# 30_PSFB_Converter.net
KiCad netlist of a schematic drawn in Altium Designer
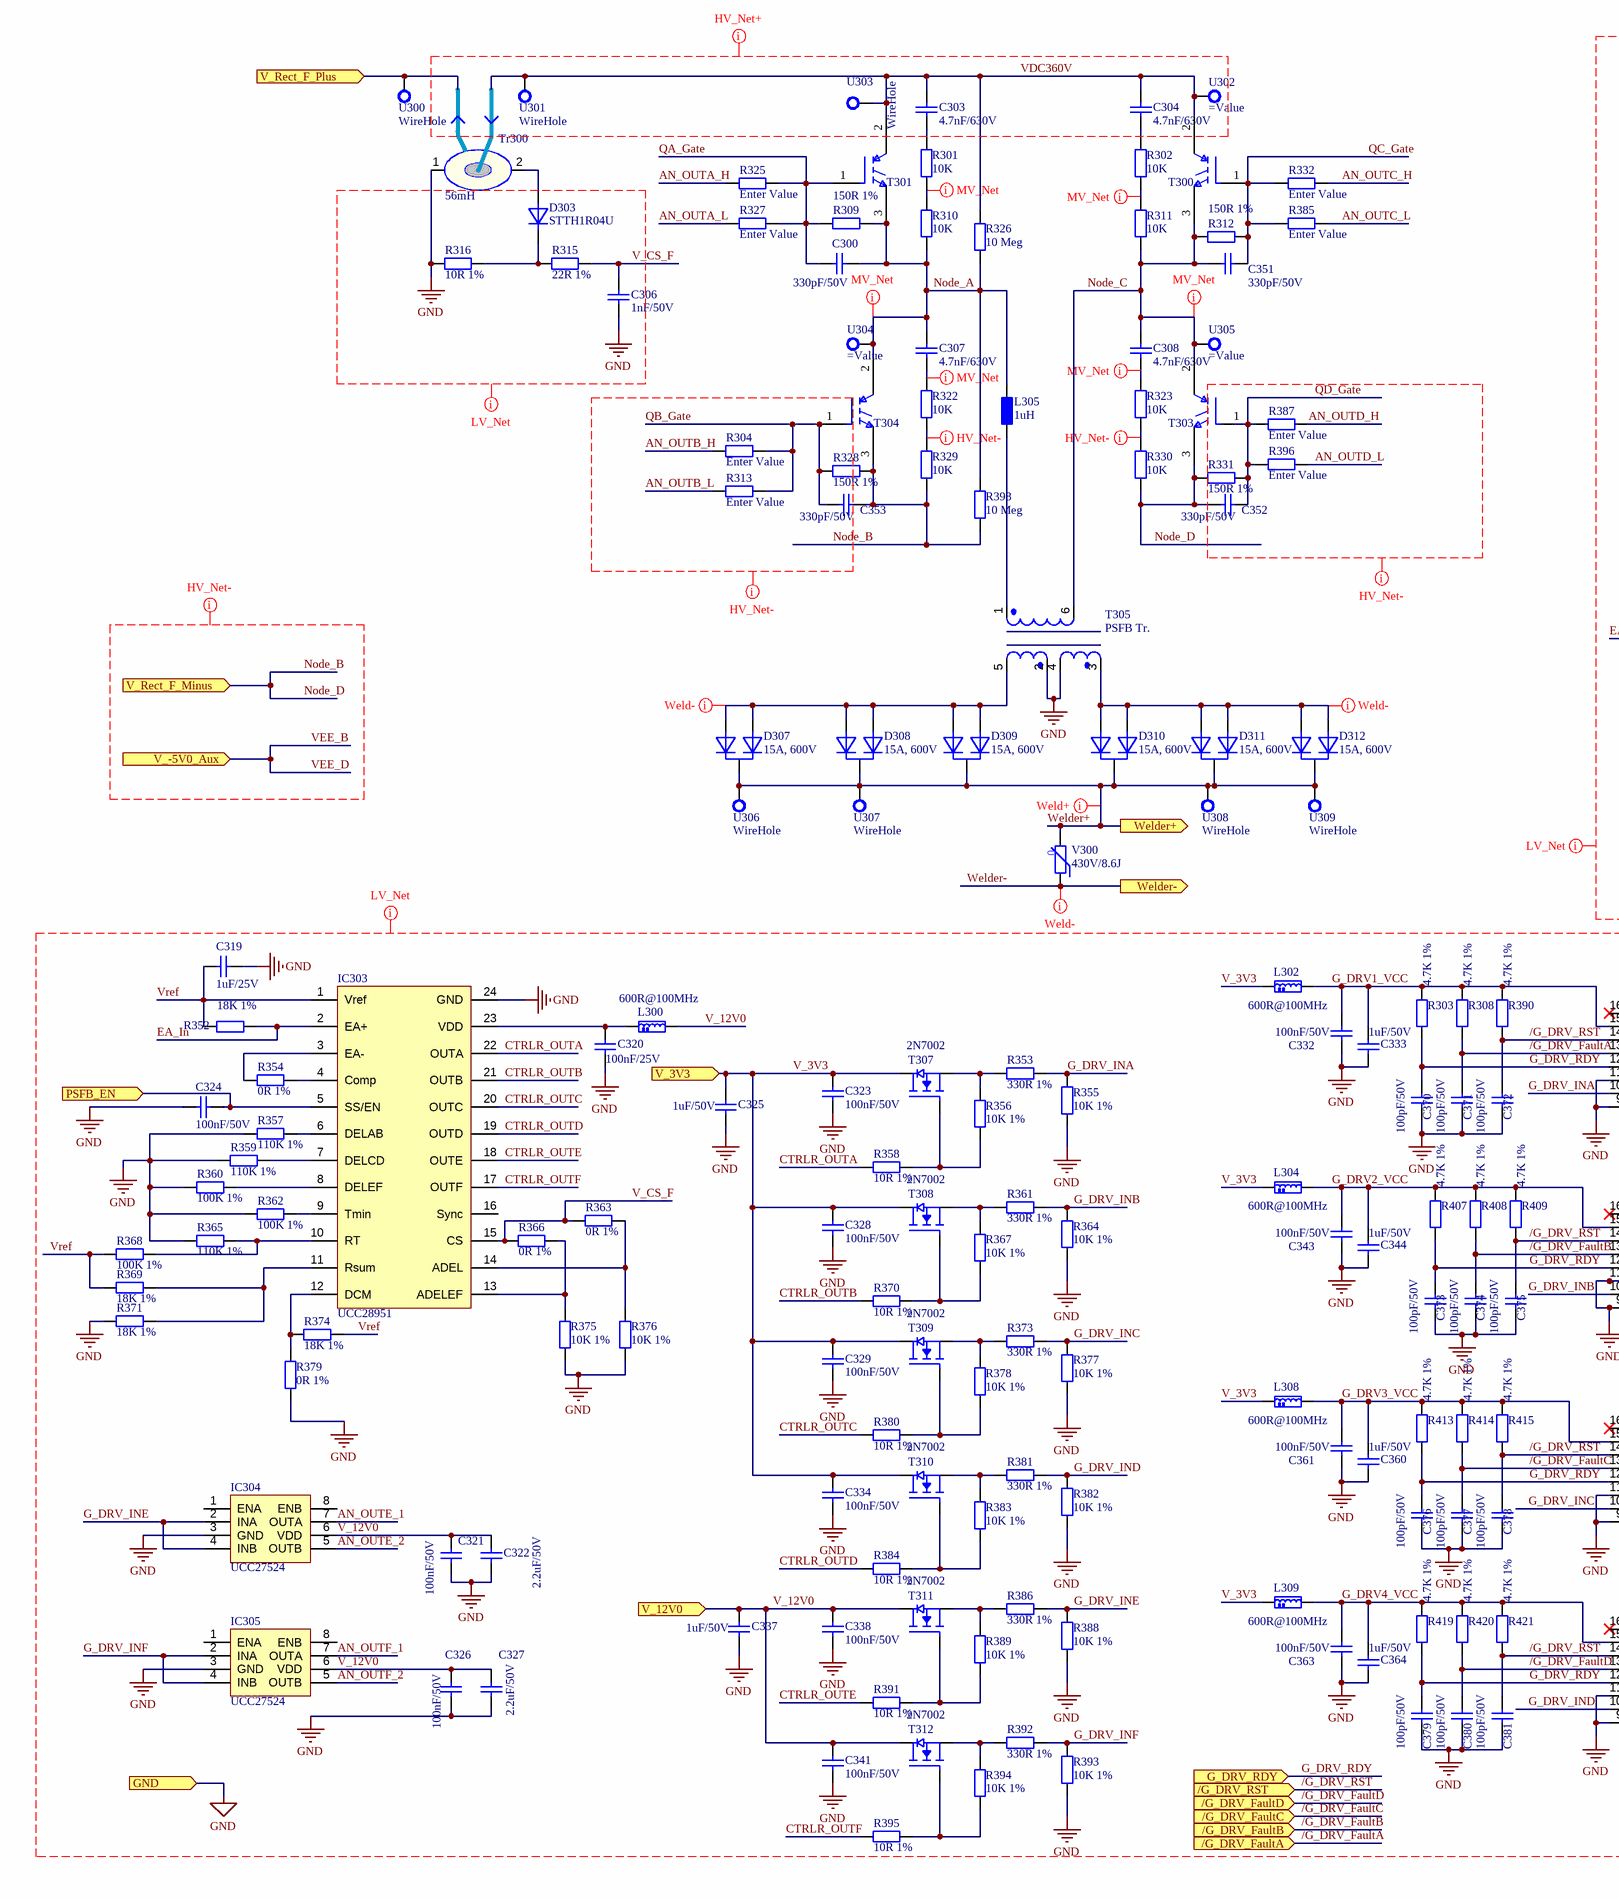
[diagram p0: 30_PSFB_Converter.SchDoc, left]
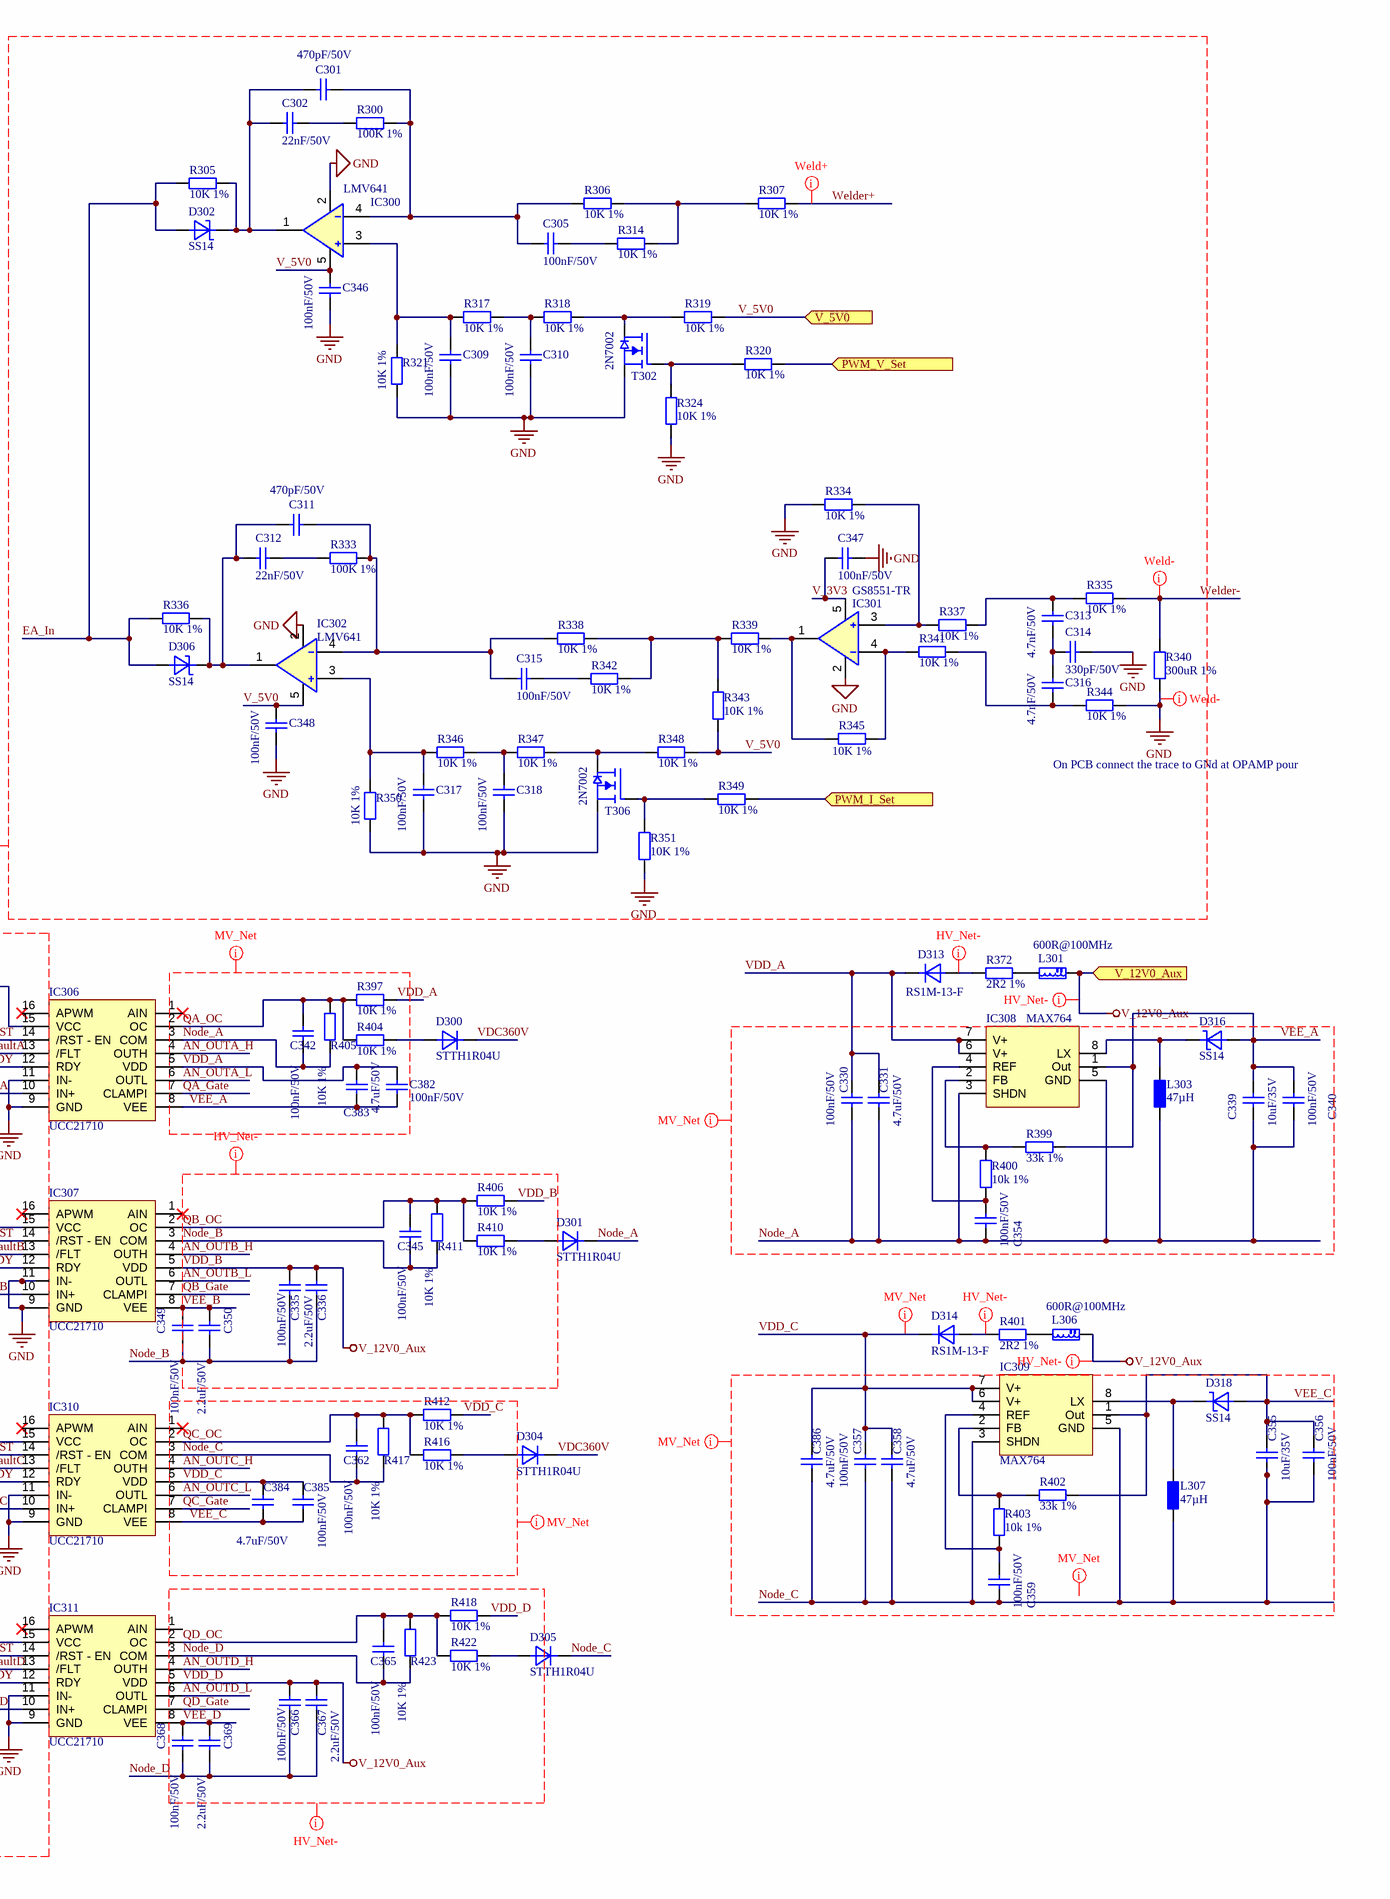
[diagram p1: 30_PSFB_Converter.SchDoc, right]

(export (version "E")
  (design (tool "Eeschema 10.0.6"))
  (components
    (comp (ref "C300")
      (value "330pF/50V")
      (footprint "EIA0603")
      (description "Generic 0603 ceramic capacitor")
      (fields (field (name "MANUFACTURER") "Open") (field (name "CREATED BY") "Hamad"))
      (libsource (lib "Amjad_Components") (part "C_Ceramic"))
    )
    (comp (ref "C301")
      (value "470pF/50V")
      (footprint "EIA0603")
      (description "Generic 0603 ceramic capacitor")
      (fields (field (name "MANUFACTURER") "Open") (field (name "CREATED BY") "Hamad"))
      (libsource (lib "Amjad_Components") (part "C_Ceramic"))
    )
    (comp (ref "C302")
      (value "22nF/50V")
      (footprint "EIA0603")
      (description "Generic 0603 ceramic capacitor")
      (fields (field (name "MANUFACTURER") "Open") (field (name "CREATED BY") "Hamad"))
      (libsource (lib "Amjad_Components") (part "C_Ceramic"))
    )
    (comp (ref "C303")
      (value "4.7nF/630V")
      (footprint "C_Disc_P5H13")
      (description "4700 pF ±10% 630V Ceramic Capacitor X7R Radial")
      (fields (field (name "MANUFACTURER") "TDK") (field (name "CREATED BY") "Hamad"))
      (libsource (lib "Amjad_Components") (part "C_Ceramic"))
    )
    (comp (ref "C304")
      (value "4.7nF/630V")
      (footprint "C_Disc_P5H13")
      (description "4700 pF ±10% 630V Ceramic Capacitor X7R Radial")
      (fields (field (name "MANUFACTURER") "TDK") (field (name "CREATED BY") "Hamad"))
      (libsource (lib "Amjad_Components") (part "C_Ceramic"))
    )
    (comp (ref "C305")
      (value "100nF/50V")
      (footprint "EIA0603")
      (description "Generic 0603 ceramic capacitor")
      (fields (field (name "MANUFACTURER") "Open") (field (name "CREATED BY") "Hamad"))
      (libsource (lib "Amjad_Components") (part "C_Ceramic"))
    )
    (comp (ref "C306")
      (value "1nF/50V")
      (footprint "EIA0603")
      (description "Generic 0603 ceramic capacitor")
      (fields (field (name "MANUFACTURER") "Open") (field (name "CREATED BY") "Hamad"))
      (libsource (lib "Amjad_Components") (part "C_Ceramic"))
    )
    (comp (ref "C307")
      (value "4.7nF/630V")
      (footprint "C_Disc_P5H13")
      (description "4700 pF ±10% 630V Ceramic Capacitor X7R Radial")
      (fields (field (name "MANUFACTURER") "TDK") (field (name "CREATED BY") "Hamad"))
      (libsource (lib "Amjad_Components") (part "C_Ceramic"))
    )
    (comp (ref "C308")
      (value "4.7nF/630V")
      (footprint "C_Disc_P5H13")
      (description "4700 pF ±10% 630V Ceramic Capacitor X7R Radial")
      (fields (field (name "MANUFACTURER") "TDK") (field (name "CREATED BY") "Hamad"))
      (libsource (lib "Amjad_Components") (part "C_Ceramic"))
    )
    (comp (ref "C309")
      (value "100nF/50V")
      (footprint "EIA0603")
      (description "Generic 0603 ceramic capacitor")
      (fields (field (name "MANUFACTURER") "Open") (field (name "CREATED BY") "Hamad"))
      (libsource (lib "Amjad_Components") (part "C_Ceramic"))
    )
    (comp (ref "C310")
      (value "100nF/50V")
      (footprint "EIA0603")
      (description "Generic 0603 ceramic capacitor")
      (fields (field (name "MANUFACTURER") "Open") (field (name "CREATED BY") "Hamad"))
      (libsource (lib "Amjad_Components") (part "C_Ceramic"))
    )
    (comp (ref "C311")
      (value "470pF/50V")
      (footprint "EIA0603")
      (description "Generic 0603 ceramic capacitor")
      (fields (field (name "MANUFACTURER") "Open") (field (name "CREATED BY") "Hamad"))
      (libsource (lib "Amjad_Components") (part "C_Ceramic"))
    )
    (comp (ref "C312")
      (value "22nF/50V")
      (footprint "EIA0603")
      (description "Generic 0603 ceramic capacitor")
      (fields (field (name "MANUFACTURER") "Open") (field (name "CREATED BY") "Hamad"))
      (libsource (lib "Amjad_Components") (part "C_Ceramic"))
    )
    (comp (ref "C313")
      (value "4.7nF/50V")
      (footprint "EIA0603")
      (description "Generic 0603 ceramic capacitor")
      (fields (field (name "MANUFACTURER") "Open") (field (name "CREATED BY") "Hamad"))
      (libsource (lib "Amjad_Components") (part "C_Ceramic"))
    )
    (comp (ref "C314")
      (value "330pF/50V")
      (footprint "EIA0603")
      (description "Generic 0603 ceramic capacitor")
      (fields (field (name "MANUFACTURER") "Open") (field (name "CREATED BY") "Hamad"))
      (libsource (lib "Amjad_Components") (part "C_Ceramic"))
    )
    (comp (ref "C315")
      (value "100nF/50V")
      (footprint "EIA0603")
      (description "Generic 0603 ceramic capacitor")
      (fields (field (name "MANUFACTURER") "Open") (field (name "CREATED BY") "Hamad"))
      (libsource (lib "Amjad_Components") (part "C_Ceramic"))
    )
    (comp (ref "C316")
      (value "4.7nF/50V")
      (footprint "EIA0603")
      (description "Generic 0603 ceramic capacitor")
      (fields (field (name "MANUFACTURER") "Open") (field (name "CREATED BY") "Hamad"))
      (libsource (lib "Amjad_Components") (part "C_Ceramic"))
    )
    (comp (ref "C317")
      (value "100nF/50V")
      (footprint "EIA0603")
      (description "Generic 0603 ceramic capacitor")
      (fields (field (name "MANUFACTURER") "Open") (field (name "CREATED BY") "Hamad"))
      (libsource (lib "Amjad_Components") (part "C_Ceramic"))
    )
    (comp (ref "C318")
      (value "100nF/50V")
      (footprint "EIA0603")
      (description "Generic 0603 ceramic capacitor")
      (fields (field (name "MANUFACTURER") "Open") (field (name "CREATED BY") "Hamad"))
      (libsource (lib "Amjad_Components") (part "C_Ceramic"))
    )
    (comp (ref "C319")
      (value "1uF/25V")
      (footprint "EIA0603")
      (description "Generic 0603 ceramic capacitor")
      (fields (field (name "MANUFACTURER") "Open") (field (name "CREATED BY") "Hamad"))
      (libsource (lib "Amjad_Components") (part "C_Ceramic"))
    )
    (comp (ref "C320")
      (value "100nF/25V")
      (footprint "EIA0603")
      (description "Generic 0603 ceramic capacitor")
      (fields (field (name "MANUFACTURER") "Open") (field (name "CREATED BY") "Hamad"))
      (libsource (lib "Amjad_Components") (part "C_Ceramic"))
    )
    (comp (ref "C321")
      (value "100nF/50V")
      (footprint "EIA0603")
      (description "Generic 0603 ceramic capacitor")
      (fields (field (name "MANUFACTURER") "Open") (field (name "CREATED BY") "Hamad"))
      (libsource (lib "Amjad_Components") (part "C_Ceramic"))
    )
    (comp (ref "C322")
      (value "2.2uF/50V")
      (footprint "EIA0603")
      (description "Generic 0603 ceramic capacitor")
      (fields (field (name "MANUFACTURER") "Open") (field (name "CREATED BY") "Hamad"))
      (libsource (lib "Amjad_Components") (part "C_Ceramic"))
    )
    (comp (ref "C323")
      (value "100nF/50V")
      (footprint "EIA0603")
      (description "Generic 0603 ceramic capacitor")
      (fields (field (name "MANUFACTURER") "Open") (field (name "CREATED BY") "Hamad"))
      (libsource (lib "Amjad_Components") (part "C_Ceramic"))
    )
    (comp (ref "C324")
      (value "100nF/50V")
      (footprint "EIA0603")
      (description "Generic 0603 ceramic capacitor")
      (fields (field (name "MANUFACTURER") "Open") (field (name "CREATED BY") "Hamad"))
      (libsource (lib "Amjad_Components") (part "C_Ceramic"))
    )
    (comp (ref "C325")
      (value "1uF/50V")
      (footprint "EIA0603")
      (description "Generic 0603 ceramic capacitor")
      (fields (field (name "MANUFACTURER") "Open") (field (name "CREATED BY") "Hamad"))
      (libsource (lib "Amjad_Components") (part "C_Ceramic"))
    )
    (comp (ref "C326")
      (value "100nF/50V")
      (footprint "EIA0603")
      (description "Generic 0603 ceramic capacitor")
      (fields (field (name "MANUFACTURER") "Open") (field (name "CREATED BY") "Hamad"))
      (libsource (lib "Amjad_Components") (part "C_Ceramic"))
    )
    (comp (ref "C327")
      (value "2.2uF/50V")
      (footprint "EIA0603")
      (description "Generic 0603 ceramic capacitor")
      (fields (field (name "MANUFACTURER") "Open") (field (name "CREATED BY") "Hamad"))
      (libsource (lib "Amjad_Components") (part "C_Ceramic"))
    )
    (comp (ref "C328")
      (value "100nF/50V")
      (footprint "EIA0603")
      (description "Generic 0603 ceramic capacitor")
      (fields (field (name "MANUFACTURER") "Open") (field (name "CREATED BY") "Hamad"))
      (libsource (lib "Amjad_Components") (part "C_Ceramic"))
    )
    (comp (ref "C329")
      (value "100nF/50V")
      (footprint "EIA0603")
      (description "Generic 0603 ceramic capacitor")
      (fields (field (name "MANUFACTURER") "Open") (field (name "CREATED BY") "Hamad"))
      (libsource (lib "Amjad_Components") (part "C_Ceramic"))
    )
    (comp (ref "C330")
      (value "100nF/50V")
      (footprint "EIA0603")
      (description "Generic 0603 ceramic capacitor")
      (fields (field (name "MANUFACTURER") "Open") (field (name "CREATED BY") "Hamad"))
      (libsource (lib "Amjad_Components") (part "C_Ceramic"))
    )
    (comp (ref "C331")
      (value "4.7uF/50V")
      (footprint "EIA0603")
      (description "Generic 0603 ceramic capacitor")
      (fields (field (name "MANUFACTURER") "Open") (field (name "CREATED BY") "Hamad"))
      (libsource (lib "Amjad_Components") (part "C_Ceramic"))
    )
    (comp (ref "C332")
      (value "100nF/50V")
      (footprint "EIA0603")
      (description "Generic 0603 ceramic capacitor")
      (fields (field (name "MANUFACTURER") "Open") (field (name "CREATED BY") "Hamad"))
      (libsource (lib "Amjad_Components") (part "C_Ceramic"))
    )
    (comp (ref "C333")
      (value "1uF/50V")
      (footprint "EIA0603")
      (description "Generic 0603 ceramic capacitor")
      (fields (field (name "MANUFACTURER") "Open") (field (name "CREATED BY") "Hamad"))
      (libsource (lib "Amjad_Components") (part "C_Ceramic"))
    )
    (comp (ref "C334")
      (value "100nF/50V")
      (footprint "EIA0603")
      (description "Generic 0603 ceramic capacitor")
      (fields (field (name "MANUFACTURER") "Open") (field (name "CREATED BY") "Hamad"))
      (libsource (lib "Amjad_Components") (part "C_Ceramic"))
    )
    (comp (ref "C335")
      (value "100nF/50V")
      (footprint "EIA0603")
      (description "Generic 0603 ceramic capacitor")
      (fields (field (name "MANUFACTURER") "Open") (field (name "CREATED BY") "Hamad"))
      (libsource (lib "Amjad_Components") (part "C_Ceramic"))
    )
    (comp (ref "C336")
      (value "2.2uF/50V")
      (footprint "EIA0603")
      (description "Generic 0603 ceramic capacitor")
      (fields (field (name "MANUFACTURER") "Open") (field (name "CREATED BY") "Hamad"))
      (libsource (lib "Amjad_Components") (part "C_Ceramic"))
    )
    (comp (ref "C337")
      (value "1uF/50V")
      (footprint "EIA0603")
      (description "Generic 0603 ceramic capacitor")
      (fields (field (name "MANUFACTURER") "Open") (field (name "CREATED BY") "Hamad"))
      (libsource (lib "Amjad_Components") (part "C_Ceramic"))
    )
    (comp (ref "C338")
      (value "100nF/50V")
      (footprint "EIA0603")
      (description "Generic 0603 ceramic capacitor")
      (fields (field (name "MANUFACTURER") "Open") (field (name "CREATED BY") "Hamad"))
      (libsource (lib "Amjad_Components") (part "C_Ceramic"))
    )
    (comp (ref "C339")
      (value "10uF/35V")
      (footprint "EIA0603")
      (description "Generic 0603 ceramic capacitor")
      (fields (field (name "MANUFACTURER") "Open") (field (name "CREATED BY") "Hamad"))
      (libsource (lib "Amjad_Components") (part "C_Ceramic"))
    )
    (comp (ref "C340")
      (value "100nF/50V")
      (footprint "EIA0603")
      (description "Generic 0603 ceramic capacitor")
      (fields (field (name "MANUFACTURER") "Open") (field (name "CREATED BY") "Hamad"))
      (libsource (lib "Amjad_Components") (part "C_Ceramic"))
    )
    (comp (ref "C341")
      (value "100nF/50V")
      (footprint "EIA0603")
      (description "Generic 0603 ceramic capacitor")
      (fields (field (name "MANUFACTURER") "Open") (field (name "CREATED BY") "Hamad"))
      (libsource (lib "Amjad_Components") (part "C_Ceramic"))
    )
    (comp (ref "C342")
      (value "100nF/50V")
      (footprint "EIA0603")
      (description "Generic 0603 ceramic capacitor")
      (fields (field (name "MANUFACTURER") "Open") (field (name "CREATED BY") "Hamad"))
      (libsource (lib "Amjad_Components") (part "C_Ceramic"))
    )
    (comp (ref "C343")
      (value "100nF/50V")
      (footprint "EIA0603")
      (description "Generic 0603 ceramic capacitor")
      (fields (field (name "MANUFACTURER") "Open") (field (name "CREATED BY") "Hamad"))
      (libsource (lib "Amjad_Components") (part "C_Ceramic"))
    )
    (comp (ref "C344")
      (value "1uF/50V")
      (footprint "EIA0603")
      (description "Generic 0603 ceramic capacitor")
      (fields (field (name "MANUFACTURER") "Open") (field (name "CREATED BY") "Hamad"))
      (libsource (lib "Amjad_Components") (part "C_Ceramic"))
    )
    (comp (ref "C345")
      (value "100nF/50V")
      (footprint "EIA0603")
      (description "Generic 0603 ceramic capacitor")
      (fields (field (name "MANUFACTURER") "Open") (field (name "CREATED BY") "Hamad"))
      (libsource (lib "Amjad_Components") (part "C_Ceramic"))
    )
    (comp (ref "C346")
      (value "100nF/50V")
      (footprint "EIA0603")
      (description "Generic 0603 ceramic capacitor")
      (fields (field (name "MANUFACTURER") "Open") (field (name "CREATED BY") "Hamad"))
      (libsource (lib "Amjad_Components") (part "C_Ceramic"))
    )
    (comp (ref "C347")
      (value "100nF/50V")
      (footprint "EIA0603")
      (description "Generic 0603 ceramic capacitor")
      (fields (field (name "MANUFACTURER") "Open") (field (name "CREATED BY") "Hamad"))
      (libsource (lib "Amjad_Components") (part "C_Ceramic"))
    )
    (comp (ref "C348")
      (value "100nF/50V")
      (footprint "EIA0603")
      (description "Generic 0603 ceramic capacitor")
      (fields (field (name "MANUFACTURER") "Open") (field (name "CREATED BY") "Hamad"))
      (libsource (lib "Amjad_Components") (part "C_Ceramic"))
    )
    (comp (ref "C349")
      (value "100nF/50V")
      (footprint "EIA0603")
      (description "Generic 0603 ceramic capacitor")
      (fields (field (name "MANUFACTURER") "Open") (field (name "CREATED BY") "Hamad"))
      (libsource (lib "Amjad_Components") (part "C_Ceramic"))
    )
    (comp (ref "C350")
      (value "2.2uF/50V")
      (footprint "EIA0603")
      (description "Generic 0603 ceramic capacitor")
      (fields (field (name "MANUFACTURER") "Open") (field (name "CREATED BY") "Hamad"))
      (libsource (lib "Amjad_Components") (part "C_Ceramic"))
    )
    (comp (ref "C351")
      (value "330pF/50V")
      (footprint "EIA0603")
      (description "Generic 0603 ceramic capacitor")
      (fields (field (name "MANUFACTURER") "Open") (field (name "CREATED BY") "Hamad"))
      (libsource (lib "Amjad_Components") (part "C_Ceramic"))
    )
    (comp (ref "C352")
      (value "330pF/50V")
      (footprint "EIA0603")
      (description "Generic 0603 ceramic capacitor")
      (fields (field (name "MANUFACTURER") "Open") (field (name "CREATED BY") "Hamad"))
      (libsource (lib "Amjad_Components") (part "C_Ceramic"))
    )
    (comp (ref "C353")
      (value "330pF/50V")
      (footprint "EIA0603")
      (description "Generic 0603 ceramic capacitor")
      (fields (field (name "MANUFACTURER") "Open") (field (name "CREATED BY") "Hamad"))
      (libsource (lib "Amjad_Components") (part "C_Ceramic"))
    )
    (comp (ref "C354")
      (value "100nF/50V")
      (footprint "EIA0603")
      (description "Generic 0603 ceramic capacitor")
      (fields (field (name "MANUFACTURER") "Open") (field (name "CREATED BY") "Hamad"))
      (libsource (lib "Amjad_Components") (part "C_Ceramic"))
    )
    (comp (ref "C355")
      (value "10uF/35V")
      (footprint "EIA0603")
      (description "Generic 0603 ceramic capacitor")
      (fields (field (name "MANUFACTURER") "Open") (field (name "CREATED BY") "Hamad"))
      (libsource (lib "Amjad_Components") (part "C_Ceramic"))
    )
    (comp (ref "C356")
      (value "100nF/50V")
      (footprint "EIA0603")
      (description "Generic 0603 ceramic capacitor")
      (fields (field (name "MANUFACTURER") "Open") (field (name "CREATED BY") "Hamad"))
      (libsource (lib "Amjad_Components") (part "C_Ceramic"))
    )
    (comp (ref "C357")
      (value "100nF/50V")
      (footprint "EIA0603")
      (description "Generic 0603 ceramic capacitor")
      (fields (field (name "MANUFACTURER") "Open") (field (name "CREATED BY") "Hamad"))
      (libsource (lib "Amjad_Components") (part "C_Ceramic"))
    )
    (comp (ref "C358")
      (value "4.7uF/50V")
      (footprint "EIA0603")
      (description "Generic 0603 ceramic capacitor")
      (fields (field (name "MANUFACTURER") "Open") (field (name "CREATED BY") "Hamad"))
      (libsource (lib "Amjad_Components") (part "C_Ceramic"))
    )
    (comp (ref "C359")
      (value "100nF/50V")
      (footprint "EIA0603")
      (description "Generic 0603 ceramic capacitor")
      (fields (field (name "MANUFACTURER") "Open") (field (name "CREATED BY") "Hamad"))
      (libsource (lib "Amjad_Components") (part "C_Ceramic"))
    )
    (comp (ref "C360")
      (value "1uF/50V")
      (footprint "EIA0603")
      (description "Generic 0603 ceramic capacitor")
      (fields (field (name "MANUFACTURER") "Open") (field (name "CREATED BY") "Hamad"))
      (libsource (lib "Amjad_Components") (part "C_Ceramic"))
    )
    (comp (ref "C361")
      (value "100nF/50V")
      (footprint "EIA0603")
      (description "Generic 0603 ceramic capacitor")
      (fields (field (name "MANUFACTURER") "Open") (field (name "CREATED BY") "Hamad"))
      (libsource (lib "Amjad_Components") (part "C_Ceramic"))
    )
    (comp (ref "C362")
      (value "100nF/50V")
      (footprint "EIA0603")
      (description "Generic 0603 ceramic capacitor")
      (fields (field (name "MANUFACTURER") "Open") (field (name "CREATED BY") "Hamad"))
      (libsource (lib "Amjad_Components") (part "C_Ceramic"))
    )
    (comp (ref "C363")
      (value "100nF/50V")
      (footprint "EIA0603")
      (description "Generic 0603 ceramic capacitor")
      (fields (field (name "MANUFACTURER") "Open") (field (name "CREATED BY") "Hamad"))
      (libsource (lib "Amjad_Components") (part "C_Ceramic"))
    )
    (comp (ref "C364")
      (value "1uF/50V")
      (footprint "EIA0603")
      (description "Generic 0603 ceramic capacitor")
      (fields (field (name "MANUFACTURER") "Open") (field (name "CREATED BY") "Hamad"))
      (libsource (lib "Amjad_Components") (part "C_Ceramic"))
    )
    (comp (ref "C365")
      (value "100nF/50V")
      (footprint "EIA0603")
      (description "Generic 0603 ceramic capacitor")
      (fields (field (name "MANUFACTURER") "Open") (field (name "CREATED BY") "Hamad"))
      (libsource (lib "Amjad_Components") (part "C_Ceramic"))
    )
    (comp (ref "C366")
      (value "100nF/50V")
      (footprint "EIA0603")
      (description "Generic 0603 ceramic capacitor")
      (fields (field (name "MANUFACTURER") "Open") (field (name "CREATED BY") "Hamad"))
      (libsource (lib "Amjad_Components") (part "C_Ceramic"))
    )
    (comp (ref "C367")
      (value "2.2uF/50V")
      (footprint "EIA0603")
      (description "Generic 0603 ceramic capacitor")
      (fields (field (name "MANUFACTURER") "Open") (field (name "CREATED BY") "Hamad"))
      (libsource (lib "Amjad_Components") (part "C_Ceramic"))
    )
    (comp (ref "C368")
      (value "100nF/50V")
      (footprint "EIA0603")
      (description "Generic 0603 ceramic capacitor")
      (fields (field (name "MANUFACTURER") "Open") (field (name "CREATED BY") "Hamad"))
      (libsource (lib "Amjad_Components") (part "C_Ceramic"))
    )
    (comp (ref "C369")
      (value "2.2uF/50V")
      (footprint "EIA0603")
      (description "Generic 0603 ceramic capacitor")
      (fields (field (name "MANUFACTURER") "Open") (field (name "CREATED BY") "Hamad"))
      (libsource (lib "Amjad_Components") (part "C_Ceramic"))
    )
    (comp (ref "C370")
      (value "100pF/50V")
      (footprint "EIA0603")
      (description "Generic 0603 ceramic capacitor")
      (fields (field (name "MANUFACTURER") "Open") (field (name "CREATED BY") "Hamad"))
      (libsource (lib "Amjad_Components") (part "C_Ceramic"))
    )
    (comp (ref "C371")
      (value "100pF/50V")
      (footprint "EIA0603")
      (description "Generic 0603 ceramic capacitor")
      (fields (field (name "MANUFACTURER") "Open") (field (name "CREATED BY") "Hamad"))
      (libsource (lib "Amjad_Components") (part "C_Ceramic"))
    )
    (comp (ref "C372")
      (value "100pF/50V")
      (footprint "EIA0603")
      (description "Generic 0603 ceramic capacitor")
      (fields (field (name "MANUFACTURER") "Open") (field (name "CREATED BY") "Hamad"))
      (libsource (lib "Amjad_Components") (part "C_Ceramic"))
    )
    (comp (ref "C373")
      (value "100pF/50V")
      (footprint "EIA0603")
      (description "Generic 0603 ceramic capacitor")
      (fields (field (name "MANUFACTURER") "Open") (field (name "CREATED BY") "Hamad"))
      (libsource (lib "Amjad_Components") (part "C_Ceramic"))
    )
    (comp (ref "C374")
      (value "100pF/50V")
      (footprint "EIA0603")
      (description "Generic 0603 ceramic capacitor")
      (fields (field (name "MANUFACTURER") "Open") (field (name "CREATED BY") "Hamad"))
      (libsource (lib "Amjad_Components") (part "C_Ceramic"))
    )
    (comp (ref "C375")
      (value "100pF/50V")
      (footprint "EIA0603")
      (description "Generic 0603 ceramic capacitor")
      (fields (field (name "MANUFACTURER") "Open") (field (name "CREATED BY") "Hamad"))
      (libsource (lib "Amjad_Components") (part "C_Ceramic"))
    )
    (comp (ref "C376")
      (value "100pF/50V")
      (footprint "EIA0603")
      (description "Generic 0603 ceramic capacitor")
      (fields (field (name "MANUFACTURER") "Open") (field (name "CREATED BY") "Hamad"))
      (libsource (lib "Amjad_Components") (part "C_Ceramic"))
    )
    (comp (ref "C377")
      (value "100pF/50V")
      (footprint "EIA0603")
      (description "Generic 0603 ceramic capacitor")
      (fields (field (name "MANUFACTURER") "Open") (field (name "CREATED BY") "Hamad"))
      (libsource (lib "Amjad_Components") (part "C_Ceramic"))
    )
    (comp (ref "C378")
      (value "100pF/50V")
      (footprint "EIA0603")
      (description "Generic 0603 ceramic capacitor")
      (fields (field (name "MANUFACTURER") "Open") (field (name "CREATED BY") "Hamad"))
      (libsource (lib "Amjad_Components") (part "C_Ceramic"))
    )
    (comp (ref "C379")
      (value "100pF/50V")
      (footprint "EIA0603")
      (description "Generic 0603 ceramic capacitor")
      (fields (field (name "MANUFACTURER") "Open") (field (name "CREATED BY") "Hamad"))
      (libsource (lib "Amjad_Components") (part "C_Ceramic"))
    )
    (comp (ref "C380")
      (value "100pF/50V")
      (footprint "EIA0603")
      (description "Generic 0603 ceramic capacitor")
      (fields (field (name "MANUFACTURER") "Open") (field (name "CREATED BY") "Hamad"))
      (libsource (lib "Amjad_Components") (part "C_Ceramic"))
    )
    (comp (ref "C381")
      (value "100pF/50V")
      (footprint "EIA0603")
      (description "Generic 0603 ceramic capacitor")
      (fields (field (name "MANUFACTURER") "Open") (field (name "CREATED BY") "Hamad"))
      (libsource (lib "Amjad_Components") (part "C_Ceramic"))
    )
    (comp (ref "C382")
      (value "100nF/50V")
      (footprint "EIA0603")
      (description "Generic 0603 ceramic capacitor")
      (fields (field (name "MANUFACTURER") "Open") (field (name "CREATED BY") "Hamad"))
      (libsource (lib "Amjad_Components") (part "C_Ceramic"))
    )
    (comp (ref "C383")
      (value "4.7uF/50V")
      (footprint "EIA0603")
      (description "Generic 0603 ceramic capacitor")
      (fields (field (name "MANUFACTURER") "Open") (field (name "CREATED BY") "Hamad"))
      (libsource (lib "Amjad_Components") (part "C_Ceramic"))
    )
    (comp (ref "C384")
      (value "4.7uF/50V")
      (footprint "EIA0603")
      (description "Generic 0603 ceramic capacitor")
      (fields (field (name "MANUFACTURER") "Open") (field (name "CREATED BY") "Hamad"))
      (libsource (lib "Amjad_Components") (part "C_Ceramic"))
    )
    (comp (ref "C385")
      (value "100nF/50V")
      (footprint "EIA0603")
      (description "Generic 0603 ceramic capacitor")
      (fields (field (name "MANUFACTURER") "Open") (field (name "CREATED BY") "Hamad"))
      (libsource (lib "Amjad_Components") (part "C_Ceramic"))
    )
    (comp (ref "C386")
      (value "4.7uF/50V")
      (footprint "EIA0603")
      (description "Generic 0603 ceramic capacitor")
      (fields (field (name "MANUFACTURER") "Open") (field (name "CREATED BY") "Hamad"))
      (libsource (lib "Amjad_Components") (part "C_Ceramic"))
    )
    (comp (ref "D300")
      (value "STTH1R04U")
      (footprint "SMB")
      (description "1A, 400V, SMB, Fast Recovery")
      (fields (field (name "MANUFACTURER") "Stmicro") (field (name "CREATED BY") "HamadA"))
      (libsource (lib "Amjad_Components") (part "Diode"))
    )
    (comp (ref "D301")
      (value "STTH1R04U")
      (footprint "SMB")
      (description "1A, 400V, SMB, Fast Recovery")
      (fields (field (name "MANUFACTURER") "Stmicro") (field (name "CREATED BY") "HamadA"))
      (libsource (lib "Amjad_Components") (part "Diode"))
    )
    (comp (ref "D302")
      (value "SS14")
      (footprint "SMA")
      (description "Schottky 1A/40V SMA")
      (fields (field (name "MANUFACTURER") "MCC") (field (name "CREATED BY") "HamadA"))
      (libsource (lib "Amjad_Components") (part "SchottkyDiode"))
    )
    (comp (ref "D303")
      (value "STTH1R04U")
      (footprint "SMB")
      (description "1A, 400V, SMB, Fast Recovery")
      (fields (field (name "MANUFACTURER") "Stmicro") (field (name "CREATED BY") "HamadA"))
      (libsource (lib "Amjad_Components") (part "Diode"))
    )
    (comp (ref "D304")
      (value "STTH1R04U")
      (footprint "SMB")
      (description "1A, 400V, SMB, Fast Recovery")
      (fields (field (name "MANUFACTURER") "Stmicro") (field (name "CREATED BY") "HamadA"))
      (libsource (lib "Amjad_Components") (part "Diode"))
    )
    (comp (ref "D305")
      (value "STTH1R04U")
      (footprint "SMB")
      (description "1A, 400V, SMB, Fast Recovery")
      (fields (field (name "MANUFACTURER") "Stmicro") (field (name "CREATED BY") "HamadA"))
      (libsource (lib "Amjad_Components") (part "Diode"))
    )
    (comp (ref "D306")
      (value "SS14")
      (footprint "SMA")
      (description "Schottky 1A/40V SMA")
      (fields (field (name "MANUFACTURER") "MCC") (field (name "CREATED BY") "HamadA"))
      (libsource (lib "Amjad_Components") (part "SchottkyDiode"))
    )
    (comp (ref "D307")
      (value "15A, 600V")
      (footprint "TO247-AD")
      (description "Dual Diode, Fast Recovery, 15A,600V, Common Cathode, TO-247AD")
      (fields (field (name "MANUFACTURER") "Vishay") (field (name "CREATED BY") "HamadA"))
      (libsource (lib "Amjad_Components") (part "DualDiode_CC_3"))
    )
    (comp (ref "D308")
      (value "15A, 600V")
      (footprint "TO247-AD")
      (description "Dual Diode, Fast Recovery, 15A,600V, Common Cathode, TO-247AD")
      (fields (field (name "MANUFACTURER") "Vishay") (field (name "CREATED BY") "HamadA"))
      (libsource (lib "Amjad_Components") (part "DualDiode_CC_3"))
    )
    (comp (ref "D309")
      (value "15A, 600V")
      (footprint "TO247-AD")
      (description "Dual Diode, Fast Recovery, 15A,600V, Common Cathode, TO-247AD")
      (fields (field (name "MANUFACTURER") "Vishay") (field (name "CREATED BY") "HamadA"))
      (libsource (lib "Amjad_Components") (part "DualDiode_CC_3"))
    )
    (comp (ref "D310")
      (value "15A, 600V")
      (footprint "TO247-AD")
      (description "Dual Diode, Fast Recovery, 15A,600V, Common Cathode, TO-247AD")
      (fields (field (name "MANUFACTURER") "Vishay") (field (name "CREATED BY") "HamadA"))
      (libsource (lib "Amjad_Components") (part "DualDiode_CC_3"))
    )
    (comp (ref "D311")
      (value "15A, 600V")
      (footprint "TO247-AD")
      (description "Dual Diode, Fast Recovery, 15A,600V, Common Cathode, TO-247AD")
      (fields (field (name "MANUFACTURER") "Vishay") (field (name "CREATED BY") "HamadA"))
      (libsource (lib "Amjad_Components") (part "DualDiode_CC_3"))
    )
    (comp (ref "D312")
      (value "15A, 600V")
      (footprint "TO247-AD")
      (description "Dual Diode, Fast Recovery, 15A,600V, Common Cathode, TO-247AD")
      (fields (field (name "MANUFACTURER") "Vishay") (field (name "CREATED BY") "HamadA"))
      (libsource (lib "Amjad_Components") (part "DualDiode_CC_3"))
    )
    (comp (ref "D313")
      (value "RS1M-13-F")
      (footprint "SMA")
      (description "1KV,1A,500ns, SMA")
      (fields (field (name "MANUFACTURER") "Diodes") (field (name "CREATED BY") "HamadA"))
      (libsource (lib "Amjad_Components") (part "Diode"))
    )
    (comp (ref "D314")
      (value "RS1M-13-F")
      (footprint "SMA")
      (description "1KV,1A,500ns, SMA")
      (fields (field (name "MANUFACTURER") "Diodes") (field (name "CREATED BY") "HamadA"))
      (libsource (lib "Amjad_Components") (part "Diode"))
    )
    (comp (ref "D316")
      (value "SS14")
      (footprint "SMA")
      (description "Schottky 1A/40V SMA")
      (fields (field (name "MANUFACTURER") "MCC") (field (name "CREATED BY") "HamadA"))
      (libsource (lib "Amjad_Components") (part "SchottkyDiode"))
    )
    (comp (ref "D318")
      (value "SS14")
      (footprint "SMA")
      (description "Schottky 1A/40V SMA")
      (fields (field (name "MANUFACTURER") "MCC") (field (name "CREATED BY") "HamadA"))
      (libsource (lib "Amjad_Components") (part "SchottkyDiode"))
    )
    (comp (ref "IC300")
      (value "LMV641")
      (footprint "SOT23-5")
      (description "1CH 10MHz 1 Low power 2.3 V/us 2.7V~12V SOT-23-5 OpAmp")
      (fields (field (name "MANUFACTURER") "Texas Instruments"))
      (libsource (lib "Amjad_Components") (part "OP-1CH"))
    )
    (comp (ref "IC301")
      (value "GS8551-TR")
      (footprint "SOT23-5")
      (description "1.8MHz 1 Zero-Drift 180uA 0.95 V/us 1.8V ~ 5.5V SOT-23-5 Precision OpAmps")
      (fields (field (name "MANUFACTURER") "Gainsil"))
      (libsource (lib "Amjad_Components") (part "OP-1CH"))
    )
    (comp (ref "IC302")
      (value "LMV641")
      (footprint "SOT23-5")
      (description "1CH 10MHz 1 Low power 2.3 V/us 2.7V~12V SOT-23-5 OpAmp")
      (fields (field (name "MANUFACTURER") "Texas Instruments"))
      (libsource (lib "Amjad_Components") (part "OP-1CH"))
    )
    (comp (ref "IC303")
      (value "UCC28951")
      (footprint "TSSOP24")
      (description "Phase Shift Full Bridge Controller, TSSOP24")
      (fields (field (name "MANUFACTURER") "Texas Instruments"))
      (libsource (lib "Amjad_Components") (part "UCC28951"))
    )
    (comp (ref "IC304")
      (value "UCC27524")
      (footprint "VSSOP-8")
      (description "Low-Side Gate Driver IC Non-Inverting 8-HVSSOP")
      (fields (field (name "MANUFACTURER") "Texas Instruments"))
      (libsource (lib "Amjad_Components") (part "UCC27524"))
    )
    (comp (ref "IC305")
      (value "UCC27524")
      (footprint "VSSOP-8")
      (description "Low-Side Gate Driver IC Non-Inverting 8-HVSSOP")
      (fields (field (name "MANUFACTURER") "Texas Instruments"))
      (libsource (lib "Amjad_Components") (part "UCC27524"))
    )
    (comp (ref "IC306")
      (value "UCC21710")
      (footprint "SOIC16_Wide_HV")
      (description "Isolated Gate Driver, 10A, 1CH, SOIC-16")
      (fields (field (name "MANUFACTURER") "Texas Instruments"))
      (libsource (lib "Amjad_Components") (part "UCC21710"))
    )
    (comp (ref "IC307")
      (value "UCC21710")
      (footprint "SOIC16_Wide_HV")
      (description "Isolated Gate Driver, 10A, 1CH, SOIC-16")
      (fields (field (name "MANUFACTURER") "Texas Instruments"))
      (libsource (lib "Amjad_Components") (part "UCC21710"))
    )
    (comp (ref "IC308")
      (value "MAX764")
      (footprint "SOIC8")
      (description "Switching Regulator, Inverting, -5V/Adj SOIC8, Vin 3-16.5V")
      (fields (field (name "MANUFACTURER") "Maxim Integrated"))
      (libsource (lib "Amjad_Components") (part "MAX764"))
    )
    (comp (ref "IC309")
      (value "MAX764")
      (footprint "SOIC8")
      (description "Switching Regulator, Inverting, -5V/Adj SOIC8, Vin 3-16.5V")
      (fields (field (name "MANUFACTURER") "Maxim Integrated"))
      (libsource (lib "Amjad_Components") (part "MAX764"))
    )
    (comp (ref "IC310")
      (value "UCC21710")
      (footprint "SOIC16_Wide_HV")
      (description "Isolated Gate Driver, 10A, 1CH, SOIC-16")
      (fields (field (name "MANUFACTURER") "Texas Instruments"))
      (libsource (lib "Amjad_Components") (part "UCC21710"))
    )
    (comp (ref "IC311")
      (value "UCC21710")
      (footprint "SOIC16_Wide_HV")
      (description "Isolated Gate Driver, 10A, 1CH, SOIC-16")
      (fields (field (name "MANUFACTURER") "Texas Instruments"))
      (libsource (lib "Amjad_Components") (part "UCC21710"))
    )
    (comp (ref "L300")
      (value "600R@100MHz")
      (footprint "Ferrite_Smd_0603")
      (description "100 OHM 3A 0603")
      (fields (field (name "MANUFACTURER") "Murata") (field (name "CREATED BY") "HamadA"))
      (libsource (lib "Amjad_Components") (part "FerriteBead_0603"))
    )
    (comp (ref "L301")
      (value "600R@100MHz")
      (footprint "Ferrite_Smd_0603")
      (description "100 OHM 3A 0603")
      (fields (field (name "MANUFACTURER") "Murata") (field (name "CREATED BY") "HamadA"))
      (libsource (lib "Amjad_Components") (part "FerriteBead_0603"))
    )
    (comp (ref "L302")
      (value "600R@100MHz")
      (footprint "Ferrite_Smd_0603")
      (description "100 OHM 3A 0603")
      (fields (field (name "MANUFACTURER") "Murata") (field (name "CREATED BY") "HamadA"))
      (libsource (lib "Amjad_Components") (part "FerriteBead_0603"))
    )
    (comp (ref "L303")
      (value "47µH")
      (footprint "SRN8040TA")
      (description "47 µH  20% 1MHz 12Q-Factor Ferrite 2A")
      (fields (field (name "MANUFACTURER") "Bourns") (field (name "CREATED BY") "HamadA"))
      (libsource (lib "Amjad_Components") (part "Inductor"))
    )
    (comp (ref "L304")
      (value "600R@100MHz")
      (footprint "Ferrite_Smd_0603")
      (description "100 OHM 3A 0603")
      (fields (field (name "MANUFACTURER") "Murata") (field (name "CREATED BY") "HamadA"))
      (libsource (lib "Amjad_Components") (part "FerriteBead_0603"))
    )
    (comp (ref "L305")
      (value "1uH")
      (footprint "SRP1770TA")
      (description "1 µH Shielded Wirewound Inductor 52 A 2mOhm Max Nonstandard")
      (fields (field (name "MANUFACTURER") "Bourns") (field (name "CREATED BY") "HamadA"))
      (libsource (lib "Amjad_Components") (part "Inductor"))
    )
    (comp (ref "L306")
      (value "600R@100MHz")
      (footprint "Ferrite_Smd_0603")
      (description "100 OHM 3A 0603")
      (fields (field (name "MANUFACTURER") "Murata") (field (name "CREATED BY") "HamadA"))
      (libsource (lib "Amjad_Components") (part "FerriteBead_0603"))
    )
    (comp (ref "L307")
      (value "47µH")
      (footprint "SRN8040TA")
      (description "47 µH  20% 1MHz 12Q-Factor Ferrite 2A")
      (fields (field (name "MANUFACTURER") "Bourns") (field (name "CREATED BY") "HamadA"))
      (libsource (lib "Amjad_Components") (part "Inductor"))
    )
    (comp (ref "L308")
      (value "600R@100MHz")
      (footprint "Ferrite_Smd_0603")
      (description "100 OHM 3A 0603")
      (fields (field (name "MANUFACTURER") "Murata") (field (name "CREATED BY") "HamadA"))
      (libsource (lib "Amjad_Components") (part "FerriteBead_0603"))
    )
    (comp (ref "L309")
      (value "600R@100MHz")
      (footprint "Ferrite_Smd_0603")
      (description "100 OHM 3A 0603")
      (fields (field (name "MANUFACTURER") "Murata") (field (name "CREATED BY") "HamadA"))
      (libsource (lib "Amjad_Components") (part "FerriteBead_0603"))
    )
    (comp (ref "R300")
      (value "100K 1%")
      (footprint "EIA0603")
      (description "Chip Resistor 0603")
      (fields (field (name "MANUFACTURER") "open source") (field (name "CREATED BY") "HamadA"))
      (libsource (lib "") (part "R_EU_1"))
    )
    (comp (ref "R301")
      (value "10K")
      (footprint "2010Resistor")
      (description "Chip Resistor 2010")
      (fields (field (name "MANUFACTURER") "open source") (field (name "CREATED BY") "HamadA"))
      (libsource (lib "Amjad_Components") (part "R_EU"))
    )
    (comp (ref "R302")
      (value "10K")
      (footprint "2010Resistor")
      (description "Chip Resistor 2010")
      (fields (field (name "MANUFACTURER") "open source") (field (name "CREATED BY") "HamadA"))
      (libsource (lib "Amjad_Components") (part "R_EU"))
    )
    (comp (ref "R303")
      (value "4.7K 1%")
      (footprint "EIA0603")
      (description "Chip Resistor 0603")
      (fields (field (name "MANUFACTURER") "open source") (field (name "CREATED BY") "HamadA"))
      (libsource (lib "") (part "R_EU_3"))
    )
    (comp (ref "R304")
      (value "Enter Value")
      (footprint "2010Resistor")
      (description "Chip Resistor 2010")
      (fields (field (name "MANUFACTURER") "open source") (field (name "CREATED BY") "HamadA"))
      (libsource (lib "") (part "R_EU_2"))
    )
    (comp (ref "R305")
      (value "10K 1%")
      (footprint "EIA0603")
      (description "Chip Resistor 0603")
      (fields (field (name "MANUFACTURER") "open source") (field (name "CREATED BY") "HamadA"))
      (libsource (lib "") (part "R_EU_1"))
    )
    (comp (ref "R306")
      (value "10K 1%")
      (footprint "EIA0603")
      (description "Chip Resistor 0603")
      (fields (field (name "MANUFACTURER") "open source") (field (name "CREATED BY") "HamadA"))
      (libsource (lib "") (part "R_EU_1"))
    )
    (comp (ref "R307")
      (value "10K 1%")
      (footprint "EIA0603")
      (description "Chip Resistor 0603")
      (fields (field (name "MANUFACTURER") "open source") (field (name "CREATED BY") "HamadA"))
      (libsource (lib "") (part "R_EU_2"))
    )
    (comp (ref "R308")
      (value "4.7K 1%")
      (footprint "EIA0603")
      (description "Chip Resistor 0603")
      (fields (field (name "MANUFACTURER") "open source") (field (name "CREATED BY") "HamadA"))
      (libsource (lib "") (part "R_EU_3"))
    )
    (comp (ref "R309")
      (value "150R 1%")
      (footprint "EIA1206")
      (description "Chip Resistor 1206")
      (fields (field (name "MANUFACTURER") "open source") (field (name "CREATED BY") "HamadA"))
      (libsource (lib "") (part "R_EU_1"))
    )
    (comp (ref "R310")
      (value "10K")
      (footprint "2010Resistor")
      (description "Chip Resistor 2010")
      (fields (field (name "MANUFACTURER") "open source") (field (name "CREATED BY") "HamadA"))
      (libsource (lib "Amjad_Components") (part "R_EU"))
    )
    (comp (ref "R311")
      (value "10K")
      (footprint "2010Resistor")
      (description "Chip Resistor 2010")
      (fields (field (name "MANUFACTURER") "open source") (field (name "CREATED BY") "HamadA"))
      (libsource (lib "Amjad_Components") (part "R_EU"))
    )
    (comp (ref "R312")
      (value "150R 1%")
      (footprint "EIA1206")
      (description "Chip Resistor 1206")
      (fields (field (name "MANUFACTURER") "open source") (field (name "CREATED BY") "HamadA"))
      (libsource (lib "Amjad_Components") (part "R_EU"))
    )
    (comp (ref "R313")
      (value "Enter Value")
      (footprint "2010Resistor")
      (description "Chip Resistor 2010")
      (fields (field (name "MANUFACTURER") "open source") (field (name "CREATED BY") "HamadA"))
      (libsource (lib "") (part "R_EU_2"))
    )
    (comp (ref "R314")
      (value "10K 1%")
      (footprint "EIA0603")
      (description "Chip Resistor 0603")
      (fields (field (name "MANUFACTURER") "open source") (field (name "CREATED BY") "HamadA"))
      (libsource (lib "") (part "R_EU_1"))
    )
    (comp (ref "R315")
      (value "22R 1%")
      (footprint "EIA0603")
      (description "Chip Resistor 0603")
      (fields (field (name "MANUFACTURER") "open source") (field (name "CREATED BY") "HamadA"))
      (libsource (lib "") (part "R_EU_1"))
    )
    (comp (ref "R316")
      (value "10R 1%")
      (footprint "EIA1206")
      (description "Chip Resistor 1206")
      (fields (field (name "MANUFACTURER") "open source") (field (name "CREATED BY") "HamadA"))
      (libsource (lib "") (part "R_EU_2"))
    )
    (comp (ref "R317")
      (value "10K 1%")
      (footprint "EIA0603")
      (description "Chip Resistor 0603")
      (fields (field (name "MANUFACTURER") "open source") (field (name "CREATED BY") "HamadA"))
      (libsource (lib "") (part "R_EU_1"))
    )
    (comp (ref "R318")
      (value "10K 1%")
      (footprint "EIA0603")
      (description "Chip Resistor 0603")
      (fields (field (name "MANUFACTURER") "open source") (field (name "CREATED BY") "HamadA"))
      (libsource (lib "") (part "R_EU_1"))
    )
    (comp (ref "R319")
      (value "10K 1%")
      (footprint "EIA0603")
      (description "Chip Resistor 0603")
      (fields (field (name "MANUFACTURER") "open source") (field (name "CREATED BY") "HamadA"))
      (libsource (lib "") (part "R_EU_2"))
    )
    (comp (ref "R320")
      (value "10K 1%")
      (footprint "EIA0603")
      (description "Chip Resistor 0603")
      (fields (field (name "MANUFACTURER") "open source") (field (name "CREATED BY") "HamadA"))
      (libsource (lib "") (part "R_EU_2"))
    )
    (comp (ref "R321")
      (value "10K 1%")
      (footprint "EIA0603")
      (description "Chip Resistor 0603")
      (fields (field (name "MANUFACTURER") "open source") (field (name "CREATED BY") "HamadA"))
      (libsource (lib "") (part "R_EU_3"))
    )
    (comp (ref "R322")
      (value "10K")
      (footprint "2010Resistor")
      (description "Chip Resistor 2010")
      (fields (field (name "MANUFACTURER") "open source") (field (name "CREATED BY") "HamadA"))
      (libsource (lib "Amjad_Components") (part "R_EU"))
    )
    (comp (ref "R323")
      (value "10K")
      (footprint "2010Resistor")
      (description "Chip Resistor 2010")
      (fields (field (name "MANUFACTURER") "open source") (field (name "CREATED BY") "HamadA"))
      (libsource (lib "Amjad_Components") (part "R_EU"))
    )
    (comp (ref "R324")
      (value "10K 1%")
      (footprint "EIA0603")
      (description "Chip Resistor 0603")
      (fields (field (name "MANUFACTURER") "open source") (field (name "CREATED BY") "HamadA"))
      (libsource (lib "Amjad_Components") (part "R_EU"))
    )
    (comp (ref "R325")
      (value "Enter Value")
      (footprint "2010Resistor")
      (description "Chip Resistor 2010")
      (fields (field (name "MANUFACTURER") "open source") (field (name "CREATED BY") "HamadA"))
      (libsource (lib "") (part "R_EU_2"))
    )
    (comp (ref "R326")
      (value "10 Meg")
      (footprint "RES-RM12.5-VR37")
      (description "Metal  Film, 1/2W, 10 Meg , 350V, 5% +/-Tol")
      (fields (field (name "MANUFACTURER") "Stack Pole Electronics") (field (name "CREATED BY") "HamadA"))
      (libsource (lib "Amjad_Components") (part "R_EU"))
    )
    (comp (ref "R327")
      (value "Enter Value")
      (footprint "2010Resistor")
      (description "Chip Resistor 2010")
      (fields (field (name "MANUFACTURER") "open source") (field (name "CREATED BY") "HamadA"))
      (libsource (lib "") (part "R_EU_2"))
    )
    (comp (ref "R328")
      (value "150R 1%")
      (footprint "EIA1206")
      (description "Chip Resistor 1206")
      (fields (field (name "MANUFACTURER") "open source") (field (name "CREATED BY") "HamadA"))
      (libsource (lib "") (part "R_EU_1"))
    )
    (comp (ref "R329")
      (value "10K")
      (footprint "2010Resistor")
      (description "Chip Resistor 2010")
      (fields (field (name "MANUFACTURER") "open source") (field (name "CREATED BY") "HamadA"))
      (libsource (lib "Amjad_Components") (part "R_EU"))
    )
    (comp (ref "R330")
      (value "10K")
      (footprint "2010Resistor")
      (description "Chip Resistor 2010")
      (fields (field (name "MANUFACTURER") "open source") (field (name "CREATED BY") "HamadA"))
      (libsource (lib "Amjad_Components") (part "R_EU"))
    )
    (comp (ref "R331")
      (value "150R 1%")
      (footprint "EIA1206")
      (description "Chip Resistor 1206")
      (fields (field (name "MANUFACTURER") "open source") (field (name "CREATED BY") "HamadA"))
      (libsource (lib "Amjad_Components") (part "R_EU"))
    )
    (comp (ref "R332")
      (value "Enter Value")
      (footprint "2010Resistor")
      (description "Chip Resistor 2010")
      (fields (field (name "MANUFACTURER") "open source") (field (name "CREATED BY") "HamadA"))
      (libsource (lib "") (part "R_EU_3"))
    )
    (comp (ref "R333")
      (value "100K 1%")
      (footprint "EIA0603")
      (description "Chip Resistor 0603")
      (fields (field (name "MANUFACTURER") "open source") (field (name "CREATED BY") "HamadA"))
      (libsource (lib "") (part "R_EU_1"))
    )
    (comp (ref "R334")
      (value "10K 1%")
      (footprint "EIA0603")
      (description "Chip Resistor 0603")
      (fields (field (name "MANUFACTURER") "open source") (field (name "CREATED BY") "HamadA"))
      (libsource (lib "") (part "R_EU_2"))
    )
    (comp (ref "R335")
      (value "10K 1%")
      (footprint "EIA0603")
      (description "Chip Resistor 0603")
      (fields (field (name "MANUFACTURER") "open source") (field (name "CREATED BY") "HamadA"))
      (libsource (lib "") (part "R_EU_2"))
    )
    (comp (ref "R336")
      (value "10K 1%")
      (footprint "EIA0603")
      (description "Chip Resistor 0603")
      (fields (field (name "MANUFACTURER") "open source") (field (name "CREATED BY") "HamadA"))
      (libsource (lib "") (part "R_EU_1"))
    )
    (comp (ref "R337")
      (value "10K 1%")
      (footprint "EIA0603")
      (description "Chip Resistor 0603")
      (fields (field (name "MANUFACTURER") "open source") (field (name "CREATED BY") "HamadA"))
      (libsource (lib "") (part "R_EU_2"))
    )
    (comp (ref "R338")
      (value "10K 1%")
      (footprint "EIA0603")
      (description "Chip Resistor 0603")
      (fields (field (name "MANUFACTURER") "open source") (field (name "CREATED BY") "HamadA"))
      (libsource (lib "") (part "R_EU_1"))
    )
    (comp (ref "R339")
      (value "10K 1%")
      (footprint "EIA0603")
      (description "Chip Resistor 0603")
      (fields (field (name "MANUFACTURER") "open source") (field (name "CREATED BY") "HamadA"))
      (libsource (lib "") (part "R_EU_2"))
    )
    (comp (ref "R340")
      (value "300uR 1%")
      (footprint "WSLP3921L")
      (description "Chip Resistor 1206")
      (fields (field (name "MANUFACTURER") "Vishay") (field (name "CREATED BY") "HamadA"))
      (libsource (lib "Amjad_Components") (part "R_EU"))
    )
    (comp (ref "R341")
      (value "10K 1%")
      (footprint "EIA0603")
      (description "Chip Resistor 0603")
      (fields (field (name "MANUFACTURER") "open source") (field (name "CREATED BY") "HamadA"))
      (libsource (lib "") (part "R_EU_2"))
    )
    (comp (ref "R342")
      (value "10K 1%")
      (footprint "EIA0603")
      (description "Chip Resistor 0603")
      (fields (field (name "MANUFACTURER") "open source") (field (name "CREATED BY") "HamadA"))
      (libsource (lib "") (part "R_EU_1"))
    )
    (comp (ref "R343")
      (value "10K 1%")
      (footprint "EIA0603")
      (description "Chip Resistor 0603")
      (fields (field (name "MANUFACTURER") "open source") (field (name "CREATED BY") "HamadA"))
      (libsource (lib "Amjad_Components") (part "R_EU"))
    )
    (comp (ref "R344")
      (value "10K 1%")
      (footprint "EIA0603")
      (description "Chip Resistor 0603")
      (fields (field (name "MANUFACTURER") "open source") (field (name "CREATED BY") "HamadA"))
      (libsource (lib "") (part "R_EU_2"))
    )
    (comp (ref "R345")
      (value "10K 1%")
      (footprint "EIA0603")
      (description "Chip Resistor 0603")
      (fields (field (name "MANUFACTURER") "open source") (field (name "CREATED BY") "HamadA"))
      (libsource (lib "") (part "R_EU_1"))
    )
    (comp (ref "R346")
      (value "10K 1%")
      (footprint "EIA0603")
      (description "Chip Resistor 0603")
      (fields (field (name "MANUFACTURER") "open source") (field (name "CREATED BY") "HamadA"))
      (libsource (lib "") (part "R_EU_1"))
    )
    (comp (ref "R347")
      (value "10K 1%")
      (footprint "EIA0603")
      (description "Chip Resistor 0603")
      (fields (field (name "MANUFACTURER") "open source") (field (name "CREATED BY") "HamadA"))
      (libsource (lib "") (part "R_EU_1"))
    )
    (comp (ref "R348")
      (value "10K 1%")
      (footprint "EIA0603")
      (description "Chip Resistor 0603")
      (fields (field (name "MANUFACTURER") "open source") (field (name "CREATED BY") "HamadA"))
      (libsource (lib "") (part "R_EU_2"))
    )
    (comp (ref "R349")
      (value "10K 1%")
      (footprint "EIA0603")
      (description "Chip Resistor 0603")
      (fields (field (name "MANUFACTURER") "open source") (field (name "CREATED BY") "HamadA"))
      (libsource (lib "") (part "R_EU_2"))
    )
    (comp (ref "R350")
      (value "10K 1%")
      (footprint "EIA0603")
      (description "Chip Resistor 0603")
      (fields (field (name "MANUFACTURER") "open source") (field (name "CREATED BY") "HamadA"))
      (libsource (lib "") (part "R_EU_3"))
    )
    (comp (ref "R351")
      (value "10K 1%")
      (footprint "EIA0603")
      (description "Chip Resistor 0603")
      (fields (field (name "MANUFACTURER") "open source") (field (name "CREATED BY") "HamadA"))
      (libsource (lib "Amjad_Components") (part "R_EU"))
    )
    (comp (ref "R352")
      (value "18K 1%")
      (footprint "EIA0603")
      (description "Chip Resistor 0603")
      (fields (field (name "MANUFACTURER") "open source") (field (name "CREATED BY") "HamadA"))
      (libsource (lib "") (part "R_EU_2"))
    )
    (comp (ref "R353")
      (value "330R 1%")
      (footprint "EIA0603")
      (description "Chip Resistor 0603")
      (fields (field (name "MANUFACTURER") "open source") (field (name "CREATED BY") "HamadA"))
      (libsource (lib "") (part "R_EU_1"))
    )
    (comp (ref "R354")
      (value "0R 1%")
      (footprint "EIA0603")
      (description "Chip Resistor 0603")
      (fields (field (name "MANUFACTURER") "open source") (field (name "CREATED BY") "HamadA"))
      (libsource (lib "") (part "R_EU_2"))
    )
    (comp (ref "R355")
      (value "10K 1%")
      (footprint "EIA0603")
      (description "Chip Resistor 0603")
      (fields (field (name "MANUFACTURER") "open source") (field (name "CREATED BY") "HamadA"))
      (libsource (lib "") (part "R_EU_3"))
    )
    (comp (ref "R356")
      (value "10K 1%")
      (footprint "EIA0603")
      (description "Chip Resistor 0603")
      (fields (field (name "MANUFACTURER") "open source") (field (name "CREATED BY") "HamadA"))
      (libsource (lib "Amjad_Components") (part "R_EU"))
    )
    (comp (ref "R357")
      (value "110K 1%")
      (footprint "EIA0603")
      (description "Chip Resistor 0603")
      (fields (field (name "MANUFACTURER") "open source") (field (name "CREATED BY") "HamadA"))
      (libsource (lib "") (part "R_EU_2"))
    )
    (comp (ref "R358")
      (value "10R 1%")
      (footprint "EIA0603")
      (description "Chip Resistor 0603")
      (fields (field (name "MANUFACTURER") "open source") (field (name "CREATED BY") "HamadA"))
      (libsource (lib "") (part "R_EU_2"))
    )
    (comp (ref "R359")
      (value "110K 1%")
      (footprint "EIA0603")
      (description "Chip Resistor 0603")
      (fields (field (name "MANUFACTURER") "open source") (field (name "CREATED BY") "HamadA"))
      (libsource (lib "") (part "R_EU_2"))
    )
    (comp (ref "R360")
      (value "100K 1%")
      (footprint "EIA0603")
      (description "Chip Resistor 0603")
      (fields (field (name "MANUFACTURER") "open source") (field (name "CREATED BY") "HamadA"))
      (libsource (lib "") (part "R_EU_2"))
    )
    (comp (ref "R361")
      (value "330R 1%")
      (footprint "EIA0603")
      (description "Chip Resistor 0603")
      (fields (field (name "MANUFACTURER") "open source") (field (name "CREATED BY") "HamadA"))
      (libsource (lib "") (part "R_EU_1"))
    )
    (comp (ref "R362")
      (value "100K 1%")
      (footprint "EIA0603")
      (description "Chip Resistor 0603")
      (fields (field (name "MANUFACTURER") "open source") (field (name "CREATED BY") "HamadA"))
      (libsource (lib "") (part "R_EU_2"))
    )
    (comp (ref "R363")
      (value "0R 1%")
      (footprint "EIA0603")
      (description "Chip Resistor 0603")
      (fields (field (name "MANUFACTURER") "open source") (field (name "CREATED BY") "HamadA"))
      (libsource (lib "") (part "R_EU_2"))
    )
    (comp (ref "R364")
      (value "10K 1%")
      (footprint "EIA0603")
      (description "Chip Resistor 0603")
      (fields (field (name "MANUFACTURER") "open source") (field (name "CREATED BY") "HamadA"))
      (libsource (lib "") (part "R_EU_3"))
    )
    (comp (ref "R365")
      (value "110K 1%")
      (footprint "EIA0603")
      (description "Chip Resistor 0603")
      (fields (field (name "MANUFACTURER") "open source") (field (name "CREATED BY") "HamadA"))
      (libsource (lib "") (part "R_EU_1"))
    )
    (comp (ref "R366")
      (value "0R 1%")
      (footprint "EIA0603")
      (description "Chip Resistor 0603")
      (fields (field (name "MANUFACTURER") "open source") (field (name "CREATED BY") "HamadA"))
      (libsource (lib "") (part "R_EU_2"))
    )
    (comp (ref "R367")
      (value "10K 1%")
      (footprint "EIA0603")
      (description "Chip Resistor 0603")
      (fields (field (name "MANUFACTURER") "open source") (field (name "CREATED BY") "HamadA"))
      (libsource (lib "Amjad_Components") (part "R_EU"))
    )
    (comp (ref "R368")
      (value "100K 1%")
      (footprint "EIA0603")
      (description "Chip Resistor 0603")
      (fields (field (name "MANUFACTURER") "open source") (field (name "CREATED BY") "HamadA"))
      (libsource (lib "") (part "R_EU_1"))
    )
    (comp (ref "R369")
      (value "18K 1%")
      (footprint "EIA0603")
      (description "Chip Resistor 0603")
      (fields (field (name "MANUFACTURER") "open source") (field (name "CREATED BY") "HamadA"))
      (libsource (lib "") (part "R_EU_2"))
    )
    (comp (ref "R370")
      (value "10R 1%")
      (footprint "EIA0603")
      (description "Chip Resistor 0603")
      (fields (field (name "MANUFACTURER") "open source") (field (name "CREATED BY") "HamadA"))
      (libsource (lib "") (part "R_EU_2"))
    )
    (comp (ref "R371")
      (value "18K 1%")
      (footprint "EIA0603")
      (description "Chip Resistor 0603")
      (fields (field (name "MANUFACTURER") "open source") (field (name "CREATED BY") "HamadA"))
      (libsource (lib "") (part "R_EU_2"))
    )
    (comp (ref "R372")
      (value "2R2 1%")
      (footprint "EIA1206")
      (description "Chip Resistor 1206")
      (fields (field (name "MANUFACTURER") "open source") (field (name "CREATED BY") "HamadA"))
      (libsource (lib "") (part "R_EU_2"))
    )
    (comp (ref "R373")
      (value "330R 1%")
      (footprint "EIA0603")
      (description "Chip Resistor 0603")
      (fields (field (name "MANUFACTURER") "open source") (field (name "CREATED BY") "HamadA"))
      (libsource (lib "") (part "R_EU_1"))
    )
    (comp (ref "R374")
      (value "18K 1%")
      (footprint "EIA0603")
      (description "Chip Resistor 0603")
      (fields (field (name "MANUFACTURER") "open source") (field (name "CREATED BY") "HamadA"))
      (libsource (lib "") (part "R_EU_2"))
    )
    (comp (ref "R375")
      (value "10K 1%")
      (footprint "EIA0603")
      (description "Chip Resistor 0603")
      (fields (field (name "MANUFACTURER") "open source") (field (name "CREATED BY") "HamadA"))
      (libsource (lib "Amjad_Components") (part "R_EU"))
    )
    (comp (ref "R376")
      (value "10K 1%")
      (footprint "EIA0603")
      (description "Chip Resistor 0603")
      (fields (field (name "MANUFACTURER") "open source") (field (name "CREATED BY") "HamadA"))
      (libsource (lib "Amjad_Components") (part "R_EU"))
    )
    (comp (ref "R377")
      (value "10K 1%")
      (footprint "EIA0603")
      (description "Chip Resistor 0603")
      (fields (field (name "MANUFACTURER") "open source") (field (name "CREATED BY") "HamadA"))
      (libsource (lib "") (part "R_EU_3"))
    )
    (comp (ref "R378")
      (value "10K 1%")
      (footprint "EIA0603")
      (description "Chip Resistor 0603")
      (fields (field (name "MANUFACTURER") "open source") (field (name "CREATED BY") "HamadA"))
      (libsource (lib "Amjad_Components") (part "R_EU"))
    )
    (comp (ref "R379")
      (value "0R 1%")
      (footprint "EIA0603")
      (description "Chip Resistor 0603")
      (fields (field (name "MANUFACTURER") "open source") (field (name "CREATED BY") "HamadA"))
      (libsource (lib "") (part "R_EU_3"))
    )
    (comp (ref "R380")
      (value "10R 1%")
      (footprint "EIA0603")
      (description "Chip Resistor 0603")
      (fields (field (name "MANUFACTURER") "open source") (field (name "CREATED BY") "HamadA"))
      (libsource (lib "") (part "R_EU_2"))
    )
    (comp (ref "R381")
      (value "330R 1%")
      (footprint "EIA0603")
      (description "Chip Resistor 0603")
      (fields (field (name "MANUFACTURER") "open source") (field (name "CREATED BY") "HamadA"))
      (libsource (lib "") (part "R_EU_1"))
    )
    (comp (ref "R382")
      (value "10K 1%")
      (footprint "EIA0603")
      (description "Chip Resistor 0603")
      (fields (field (name "MANUFACTURER") "open source") (field (name "CREATED BY") "HamadA"))
      (libsource (lib "") (part "R_EU_3"))
    )
    (comp (ref "R383")
      (value "10K 1%")
      (footprint "EIA0603")
      (description "Chip Resistor 0603")
      (fields (field (name "MANUFACTURER") "open source") (field (name "CREATED BY") "HamadA"))
      (libsource (lib "Amjad_Components") (part "R_EU"))
    )
    (comp (ref "R384")
      (value "10R 1%")
      (footprint "EIA0603")
      (description "Chip Resistor 0603")
      (fields (field (name "MANUFACTURER") "open source") (field (name "CREATED BY") "HamadA"))
      (libsource (lib "") (part "R_EU_2"))
    )
    (comp (ref "R385")
      (value "Enter Value")
      (footprint "2010Resistor")
      (description "Chip Resistor 2010")
      (fields (field (name "MANUFACTURER") "open source") (field (name "CREATED BY") "HamadA"))
      (libsource (lib "") (part "R_EU_3"))
    )
    (comp (ref "R386")
      (value "330R 1%")
      (footprint "EIA0603")
      (description "Chip Resistor 0603")
      (fields (field (name "MANUFACTURER") "open source") (field (name "CREATED BY") "HamadA"))
      (libsource (lib "") (part "R_EU_1"))
    )
    (comp (ref "R387")
      (value "Enter Value")
      (footprint "2010Resistor")
      (description "Chip Resistor 2010")
      (fields (field (name "MANUFACTURER") "open source") (field (name "CREATED BY") "HamadA"))
      (libsource (lib "") (part "R_EU_3"))
    )
    (comp (ref "R388")
      (value "10K 1%")
      (footprint "EIA0603")
      (description "Chip Resistor 0603")
      (fields (field (name "MANUFACTURER") "open source") (field (name "CREATED BY") "HamadA"))
      (libsource (lib "") (part "R_EU_3"))
    )
    (comp (ref "R389")
      (value "10K 1%")
      (footprint "EIA0603")
      (description "Chip Resistor 0603")
      (fields (field (name "MANUFACTURER") "open source") (field (name "CREATED BY") "HamadA"))
      (libsource (lib "Amjad_Components") (part "R_EU"))
    )
    (comp (ref "R390")
      (value "4.7K 1%")
      (footprint "EIA0603")
      (description "Chip Resistor 0603")
      (fields (field (name "MANUFACTURER") "open source") (field (name "CREATED BY") "HamadA"))
      (libsource (lib "") (part "R_EU_3"))
    )
    (comp (ref "R391")
      (value "10R 1%")
      (footprint "EIA0603")
      (description "Chip Resistor 0603")
      (fields (field (name "MANUFACTURER") "open source") (field (name "CREATED BY") "HamadA"))
      (libsource (lib "") (part "R_EU_2"))
    )
    (comp (ref "R392")
      (value "330R 1%")
      (footprint "EIA0603")
      (description "Chip Resistor 0603")
      (fields (field (name "MANUFACTURER") "open source") (field (name "CREATED BY") "HamadA"))
      (libsource (lib "") (part "R_EU_1"))
    )
    (comp (ref "R393")
      (value "10K 1%")
      (footprint "EIA0603")
      (description "Chip Resistor 0603")
      (fields (field (name "MANUFACTURER") "open source") (field (name "CREATED BY") "HamadA"))
      (libsource (lib "") (part "R_EU_3"))
    )
    (comp (ref "R394")
      (value "10K 1%")
      (footprint "EIA0603")
      (description "Chip Resistor 0603")
      (fields (field (name "MANUFACTURER") "open source") (field (name "CREATED BY") "HamadA"))
      (libsource (lib "Amjad_Components") (part "R_EU"))
    )
    (comp (ref "R395")
      (value "10R 1%")
      (footprint "EIA0603")
      (description "Chip Resistor 0603")
      (fields (field (name "MANUFACTURER") "open source") (field (name "CREATED BY") "HamadA"))
      (libsource (lib "") (part "R_EU_2"))
    )
    (comp (ref "R396")
      (value "Enter Value")
      (footprint "2010Resistor")
      (description "Chip Resistor 2010")
      (fields (field (name "MANUFACTURER") "open source") (field (name "CREATED BY") "HamadA"))
      (libsource (lib "") (part "R_EU_3"))
    )
    (comp (ref "R397")
      (value "10K 1%")
      (footprint "EIA0603")
      (description "Chip Resistor 0603")
      (fields (field (name "MANUFACTURER") "open source") (field (name "CREATED BY") "HamadA"))
      (libsource (lib "") (part "R_EU_2"))
    )
    (comp (ref "R398")
      (value "10 Meg")
      (footprint "RES-RM12.5-VR37")
      (description "Metal  Film, 1/2W, 10 Meg , 350V, 5% +/-Tol")
      (fields (field (name "MANUFACTURER") "Stack Pole Electronics") (field (name "CREATED BY") "HamadA"))
      (libsource (lib "Amjad_Components") (part "R_EU"))
    )
    (comp (ref "R399")
      (value "33k 1%")
      (footprint "EIA1206")
      (description "Chip Resistor 1206")
      (fields (field (name "MANUFACTURER") "open source") (field (name "CREATED BY") "HamadA"))
      (libsource (lib "") (part "R_EU_1"))
    )
    (comp (ref "R400")
      (value "10k 1%")
      (footprint "EIA1206")
      (description "Chip Resistor 1206")
      (fields (field (name "MANUFACTURER") "open source") (field (name "CREATED BY") "HamadA"))
      (libsource (lib "Amjad_Components") (part "R_EU"))
    )
    (comp (ref "R401")
      (value "2R2 1%")
      (footprint "EIA1206")
      (description "Chip Resistor 1206")
      (fields (field (name "MANUFACTURER") "open source") (field (name "CREATED BY") "HamadA"))
      (libsource (lib "") (part "R_EU_2"))
    )
    (comp (ref "R402")
      (value "33k 1%")
      (footprint "EIA1206")
      (description "Chip Resistor 1206")
      (fields (field (name "MANUFACTURER") "open source") (field (name "CREATED BY") "HamadA"))
      (libsource (lib "") (part "R_EU_1"))
    )
    (comp (ref "R403")
      (value "10k 1%")
      (footprint "EIA1206")
      (description "Chip Resistor 1206")
      (fields (field (name "MANUFACTURER") "open source") (field (name "CREATED BY") "HamadA"))
      (libsource (lib "Amjad_Components") (part "R_EU"))
    )
    (comp (ref "R404")
      (value "10K 1%")
      (footprint "EIA0603")
      (description "Chip Resistor 0603")
      (fields (field (name "MANUFACTURER") "open source") (field (name "CREATED BY") "HamadA"))
      (libsource (lib "") (part "R_EU_2"))
    )
    (comp (ref "R405")
      (value "10K 1%")
      (footprint "EIA0603")
      (description "Chip Resistor 0603")
      (fields (field (name "MANUFACTURER") "open source") (field (name "CREATED BY") "HamadA"))
      (libsource (lib "") (part "R_EU_3"))
    )
    (comp (ref "R406")
      (value "10K 1%")
      (footprint "EIA0603")
      (description "Chip Resistor 0603")
      (fields (field (name "MANUFACTURER") "open source") (field (name "CREATED BY") "HamadA"))
      (libsource (lib "") (part "R_EU_2"))
    )
    (comp (ref "R407")
      (value "4.7K 1%")
      (footprint "EIA0603")
      (description "Chip Resistor 0603")
      (fields (field (name "MANUFACTURER") "open source") (field (name "CREATED BY") "HamadA"))
      (libsource (lib "") (part "R_EU_3"))
    )
    (comp (ref "R408")
      (value "4.7K 1%")
      (footprint "EIA0603")
      (description "Chip Resistor 0603")
      (fields (field (name "MANUFACTURER") "open source") (field (name "CREATED BY") "HamadA"))
      (libsource (lib "") (part "R_EU_3"))
    )
    (comp (ref "R409")
      (value "4.7K 1%")
      (footprint "EIA0603")
      (description "Chip Resistor 0603")
      (fields (field (name "MANUFACTURER") "open source") (field (name "CREATED BY") "HamadA"))
      (libsource (lib "") (part "R_EU_3"))
    )
    (comp (ref "R410")
      (value "10K 1%")
      (footprint "EIA0603")
      (description "Chip Resistor 0603")
      (fields (field (name "MANUFACTURER") "open source") (field (name "CREATED BY") "HamadA"))
      (libsource (lib "") (part "R_EU_2"))
    )
    (comp (ref "R411")
      (value "10K 1%")
      (footprint "EIA0603")
      (description "Chip Resistor 0603")
      (fields (field (name "MANUFACTURER") "open source") (field (name "CREATED BY") "HamadA"))
      (libsource (lib "") (part "R_EU_3"))
    )
    (comp (ref "R412")
      (value "10K 1%")
      (footprint "EIA0603")
      (description "Chip Resistor 0603")
      (fields (field (name "MANUFACTURER") "open source") (field (name "CREATED BY") "HamadA"))
      (libsource (lib "") (part "R_EU_2"))
    )
    (comp (ref "R413")
      (value "4.7K 1%")
      (footprint "EIA0603")
      (description "Chip Resistor 0603")
      (fields (field (name "MANUFACTURER") "open source") (field (name "CREATED BY") "HamadA"))
      (libsource (lib "") (part "R_EU_3"))
    )
    (comp (ref "R414")
      (value "4.7K 1%")
      (footprint "EIA0603")
      (description "Chip Resistor 0603")
      (fields (field (name "MANUFACTURER") "open source") (field (name "CREATED BY") "HamadA"))
      (libsource (lib "") (part "R_EU_3"))
    )
    (comp (ref "R415")
      (value "4.7K 1%")
      (footprint "EIA0603")
      (description "Chip Resistor 0603")
      (fields (field (name "MANUFACTURER") "open source") (field (name "CREATED BY") "HamadA"))
      (libsource (lib "") (part "R_EU_3"))
    )
    (comp (ref "R416")
      (value "10K 1%")
      (footprint "EIA0603")
      (description "Chip Resistor 0603")
      (fields (field (name "MANUFACTURER") "open source") (field (name "CREATED BY") "HamadA"))
      (libsource (lib "") (part "R_EU_2"))
    )
    (comp (ref "R417")
      (value "10K 1%")
      (footprint "EIA0603")
      (description "Chip Resistor 0603")
      (fields (field (name "MANUFACTURER") "open source") (field (name "CREATED BY") "HamadA"))
      (libsource (lib "") (part "R_EU_3"))
    )
    (comp (ref "R418")
      (value "10K 1%")
      (footprint "EIA0603")
      (description "Chip Resistor 0603")
      (fields (field (name "MANUFACTURER") "open source") (field (name "CREATED BY") "HamadA"))
      (libsource (lib "") (part "R_EU_2"))
    )
    (comp (ref "R419")
      (value "4.7K 1%")
      (footprint "EIA0603")
      (description "Chip Resistor 0603")
      (fields (field (name "MANUFACTURER") "open source") (field (name "CREATED BY") "HamadA"))
      (libsource (lib "") (part "R_EU_3"))
    )
    (comp (ref "R420")
      (value "4.7K 1%")
      (footprint "EIA0603")
      (description "Chip Resistor 0603")
      (fields (field (name "MANUFACTURER") "open source") (field (name "CREATED BY") "HamadA"))
      (libsource (lib "") (part "R_EU_3"))
    )
    (comp (ref "R421")
      (value "4.7K 1%")
      (footprint "EIA0603")
      (description "Chip Resistor 0603")
      (fields (field (name "MANUFACTURER") "open source") (field (name "CREATED BY") "HamadA"))
      (libsource (lib "") (part "R_EU_3"))
    )
    (comp (ref "R422")
      (value "10K 1%")
      (footprint "EIA0603")
      (description "Chip Resistor 0603")
      (fields (field (name "MANUFACTURER") "open source") (field (name "CREATED BY") "HamadA"))
      (libsource (lib "") (part "R_EU_2"))
    )
    (comp (ref "R423")
      (value "10K 1%")
      (footprint "EIA0603")
      (description "Chip Resistor 0603")
      (fields (field (name "MANUFACTURER") "open source") (field (name "CREATED BY") "HamadA"))
      (libsource (lib "") (part "R_EU_3"))
    )
    (comp (ref "T300")
      (value "STGW30H60DFB")
      (footprint "TO247-AC")
      (description "IGBT Trench Field Stop 600 V 60 A 260 W THT  TO-247AC")
      (fields
        (field (name "MANUFACTURER") "ST")
        (field (name "ALTERNATIVE PART") "No")
        (field (name "CREATED BY") "HamadA")
      )
      (libsource (lib "Amjad_Components") (part "IGBT"))
    )
    (comp (ref "T301")
      (value "STGW30H60DFB")
      (footprint "TO247-AC")
      (description "IGBT Trench Field Stop 600 V 60 A 260 W THT  TO-247AC")
      (fields
        (field (name "MANUFACTURER") "ST")
        (field (name "ALTERNATIVE PART") "No")
        (field (name "CREATED BY") "HamadA")
      )
      (libsource (lib "Amjad_Components") (part "IGBT"))
    )
    (comp (ref "T302")
      (value "2N7002")
      (footprint "SOT23-3N")
      (description "N Channel 60V 0.5A, Vthd=2.5V , 350mW")
      (fields
        (field (name "MANUFACTURER") "Diodes,NXP")
        (field (name "ALTERNATIVE PART") "No")
        (field (name "CREATED BY") "HamadA")
      )
      (libsource (lib "Amjad_Components") (part "MOSFETN"))
    )
    (comp (ref "T303")
      (value "STGW30H60DFB")
      (footprint "TO247-AC")
      (description "IGBT Trench Field Stop 600 V 60 A 260 W THT  TO-247AC")
      (fields
        (field (name "MANUFACTURER") "ST")
        (field (name "ALTERNATIVE PART") "No")
        (field (name "CREATED BY") "HamadA")
      )
      (libsource (lib "Amjad_Components") (part "IGBT"))
    )
    (comp (ref "T304")
      (value "STGW30H60DFB")
      (footprint "TO247-AC")
      (description "IGBT Trench Field Stop 600 V 60 A 260 W THT  TO-247AC")
      (fields
        (field (name "MANUFACTURER") "ST")
        (field (name "ALTERNATIVE PART") "No")
        (field (name "CREATED BY") "HamadA")
      )
      (libsource (lib "Amjad_Components") (part "IGBT"))
    )
    (comp (ref "T305")
      (value "PSFB Tr.")
      (footprint "11-0060-A")
      (description "60KHz, PSFB Transformer, 200VAC, 2 Outputs, 4KW,Chinese")
      (fields (field (name "MANUFACTURER") "Dongguan Speed Co.") (field (name "CREATED BY") "HamadA"))
      (libsource (lib "Amjad_Components") (part "11-0060-A"))
    )
    (comp (ref "T306")
      (value "2N7002")
      (footprint "SOT23-3N")
      (description "N Channel 60V 0.5A, Vthd=2.5V , 350mW")
      (fields
        (field (name "MANUFACTURER") "Diodes,NXP")
        (field (name "ALTERNATIVE PART") "No")
        (field (name "CREATED BY") "HamadA")
      )
      (libsource (lib "Amjad_Components") (part "MOSFETN"))
    )
    (comp (ref "T307")
      (value "2N7002")
      (footprint "SOT23-3N")
      (description "N Channel 60V 0.5A, Vthd=2.5V , 350mW")
      (fields
        (field (name "MANUFACTURER") "Diodes,NXP")
        (field (name "ALTERNATIVE PART") "No")
        (field (name "CREATED BY") "HamadA")
      )
      (libsource (lib "Amjad_Components") (part "MOSFETN"))
    )
    (comp (ref "T308")
      (value "2N7002")
      (footprint "SOT23-3N")
      (description "N Channel 60V 0.5A, Vthd=2.5V , 350mW")
      (fields
        (field (name "MANUFACTURER") "Diodes,NXP")
        (field (name "ALTERNATIVE PART") "No")
        (field (name "CREATED BY") "HamadA")
      )
      (libsource (lib "Amjad_Components") (part "MOSFETN"))
    )
    (comp (ref "T309")
      (value "2N7002")
      (footprint "SOT23-3N")
      (description "N Channel 60V 0.5A, Vthd=2.5V , 350mW")
      (fields
        (field (name "MANUFACTURER") "Diodes,NXP")
        (field (name "ALTERNATIVE PART") "No")
        (field (name "CREATED BY") "HamadA")
      )
      (libsource (lib "Amjad_Components") (part "MOSFETN"))
    )
    (comp (ref "T310")
      (value "2N7002")
      (footprint "SOT23-3N")
      (description "N Channel 60V 0.5A, Vthd=2.5V , 350mW")
      (fields
        (field (name "MANUFACTURER") "Diodes,NXP")
        (field (name "ALTERNATIVE PART") "No")
        (field (name "CREATED BY") "HamadA")
      )
      (libsource (lib "Amjad_Components") (part "MOSFETN"))
    )
    (comp (ref "T311")
      (value "2N7002")
      (footprint "SOT23-3N")
      (description "N Channel 60V 0.5A, Vthd=2.5V , 350mW")
      (fields
        (field (name "MANUFACTURER") "Diodes,NXP")
        (field (name "ALTERNATIVE PART") "No")
        (field (name "CREATED BY") "HamadA")
      )
      (libsource (lib "Amjad_Components") (part "MOSFETN"))
    )
    (comp (ref "T312")
      (value "2N7002")
      (footprint "SOT23-3N")
      (description "N Channel 60V 0.5A, Vthd=2.5V , 350mW")
      (fields
        (field (name "MANUFACTURER") "Diodes,NXP")
        (field (name "ALTERNATIVE PART") "No")
        (field (name "CREATED BY") "HamadA")
      )
      (libsource (lib "Amjad_Components") (part "MOSFETN"))
    )
    (comp (ref "Tr300")
      (value "56mH")
      (footprint "CST206-2A")
      (description "80 A - Current Sense Transformer 20kHz ~ 200kHz 3.5Ohm Max 56 mH THT")
      (fields (field (name "MANUFACTURER") "Triad Magnetics") (field (name "CREATED BY") "Hamad"))
      (libsource (lib "Amjad_Components") (part "Transformer-CT-2P"))
    )
    (comp (ref "U300")
      (value "WireHole")
      (footprint "PAD-3.0x6.0MM")
      (description "Wire Hole 3.0mm Dia, 6.0mm Pad.")
      (fields (field (name "MANUFACTURER") "NA") (field (name "CREATED BY") "HamadA"))
      (libsource (lib "Amjad_Components") (part "WireHole"))
    )
    (comp (ref "U301")
      (value "WireHole")
      (footprint "PAD-3.0x6.0MM")
      (description "Wire Hole 3.0mm Dia, 6.0mm Pad.")
      (fields (field (name "MANUFACTURER") "NA") (field (name "CREATED BY") "HamadA"))
      (libsource (lib "Amjad_Components") (part "WireHole"))
    )
    (comp (ref "U302")
      (value "~")
      (footprint "PAD-3.0x6.0MM")
      (description "Wire Hole 3.0mm Dia, 6.0mm Pad.")
      (fields (field (name "MANUFACTURER") "NA") (field (name "CREATED BY") "HamadA"))
      (libsource (lib "Amjad_Components") (part "WireHole"))
    )
    (comp (ref "U303")
      (value "WireHole")
      (footprint "PAD-3.0x6.0MM")
      (description "Wire Hole 3.0mm Dia, 6.0mm Pad.")
      (fields (field (name "MANUFACTURER") "NA") (field (name "CREATED BY") "HamadA"))
      (libsource (lib "Amjad_Components") (part "WireHole"))
    )
    (comp (ref "U304")
      (value "~")
      (footprint "PAD-3.0x6.0MM")
      (description "Wire Hole 3.0mm Dia, 6.0mm Pad.")
      (fields (field (name "MANUFACTURER") "NA") (field (name "CREATED BY") "HamadA"))
      (libsource (lib "Amjad_Components") (part "WireHole"))
    )
    (comp (ref "U305")
      (value "~")
      (footprint "PAD-3.0x6.0MM")
      (description "Wire Hole 3.0mm Dia, 6.0mm Pad.")
      (fields (field (name "MANUFACTURER") "NA") (field (name "CREATED BY") "HamadA"))
      (libsource (lib "Amjad_Components") (part "WireHole"))
    )
    (comp (ref "U306")
      (value "WireHole")
      (footprint "PAD-3.0x6.0MM")
      (description "Wire Hole 3.0mm Dia, 6.0mm Pad.")
      (fields (field (name "MANUFACTURER") "NA") (field (name "CREATED BY") "HamadA"))
      (libsource (lib "Amjad_Components") (part "WireHole"))
    )
    (comp (ref "U307")
      (value "WireHole")
      (footprint "PAD-3.0x6.0MM")
      (description "Wire Hole 3.0mm Dia, 6.0mm Pad.")
      (fields (field (name "MANUFACTURER") "NA") (field (name "CREATED BY") "HamadA"))
      (libsource (lib "Amjad_Components") (part "WireHole"))
    )
    (comp (ref "U308")
      (value "WireHole")
      (footprint "PAD-3.0x6.0MM")
      (description "Wire Hole 3.0mm Dia, 6.0mm Pad.")
      (fields (field (name "MANUFACTURER") "NA") (field (name "CREATED BY") "HamadA"))
      (libsource (lib "Amjad_Components") (part "WireHole"))
    )
    (comp (ref "U309")
      (value "WireHole")
      (footprint "PAD-3.0x6.0MM")
      (description "Wire Hole 3.0mm Dia, 6.0mm Pad.")
      (fields (field (name "MANUFACTURER") "NA") (field (name "CREATED BY") "HamadA"))
      (libsource (lib "Amjad_Components") (part "WireHole"))
    )
    (comp (ref "V300")
      (value "430V/8.6J")
      (footprint "EPCOS_B72205S0271K101")
      (description "430 V 400 A Varistor 1 Circuit Through Hole Disc 5mm")
      (fields (field (name "MANUFACTURER") "EPCOS") (field (name "CREATED BY") "Hamad"))
      (libsource (lib "Amjad_Components") (part "Varistor"))
    )
  )
  (nets
    (net (code "2") (name "/AN_OUTA_H") (class "Default")
      (node (ref "IC306") (pin "4") (pinfunction "OUTH_4") (pintype "passive"))
      (node (ref "R325") (pin "1") (pinfunction "1_1") (pintype "passive"))
    )
    (net (code "3") (name "/AN_OUTA_L") (class "Default")
      (node (ref "IC306") (pin "6") (pinfunction "OUTL_6") (pintype "passive"))
      (node (ref "R327") (pin "1") (pinfunction "1_1") (pintype "passive"))
    )
    (net (code "4") (name "/AN_OUTB_H") (class "Default")
      (node (ref "IC307") (pin "4") (pinfunction "OUTH_4") (pintype "passive"))
      (node (ref "R304") (pin "1") (pinfunction "1_1") (pintype "passive"))
    )
    (net (code "5") (name "/AN_OUTB_L") (class "Default")
      (node (ref "IC307") (pin "6") (pinfunction "OUTL_6") (pintype "passive"))
      (node (ref "R313") (pin "1") (pinfunction "1_1") (pintype "passive"))
    )
    (net (code "6") (name "/AN_OUTC_H") (class "Default")
      (node (ref "IC310") (pin "4") (pinfunction "OUTH_4") (pintype "passive"))
      (node (ref "R332") (pin "1") (pinfunction "1_1") (pintype "passive"))
    )
    (net (code "7") (name "/AN_OUTC_L") (class "Default")
      (node (ref "IC310") (pin "6") (pinfunction "OUTL_6") (pintype "passive"))
      (node (ref "R385") (pin "1") (pinfunction "1_1") (pintype "passive"))
    )
    (net (code "8") (name "/AN_OUTD_H") (class "Default")
      (node (ref "IC311") (pin "4") (pinfunction "OUTH_4") (pintype "passive"))
      (node (ref "R387") (pin "1") (pinfunction "1_1") (pintype "passive"))
    )
    (net (code "9") (name "/AN_OUTD_L") (class "Default")
      (node (ref "IC311") (pin "6") (pinfunction "OUTL_6") (pintype "passive"))
      (node (ref "R396") (pin "1") (pinfunction "1_1") (pintype "passive"))
    )
    (net (code "10") (name "/AN_OUTE_1") (class "Default")
      (node (ref "IC304") (pin "7") (pinfunction "OUTA_7") (pintype "passive"))
    )
    (net (code "11") (name "/AN_OUTE_2") (class "Default")
      (node (ref "IC304") (pin "5") (pinfunction "OUTB_5") (pintype "passive"))
    )
    (net (code "12") (name "/AN_OUTF_1") (class "Default")
      (node (ref "IC305") (pin "7") (pinfunction "OUTA_7") (pintype "passive"))
    )
    (net (code "13") (name "/AN_OUTF_2") (class "Default")
      (node (ref "IC305") (pin "5") (pinfunction "OUTB_5") (pintype "passive"))
    )
    (net (code "14") (name "/CTRLR_OUTA") (class "Default")
      (node (ref "IC303") (pin "22") (pinfunction "OUTA_22") (pintype "passive"))
      (node (ref "R358") (pin "1") (pinfunction "1_1") (pintype "passive"))
    )
    (net (code "15") (name "/CTRLR_OUTB") (class "Default")
      (node (ref "IC303") (pin "21") (pinfunction "OUTB_21") (pintype "passive"))
      (node (ref "R370") (pin "1") (pinfunction "1_1") (pintype "passive"))
    )
    (net (code "16") (name "/CTRLR_OUTC") (class "Default")
      (node (ref "IC303") (pin "20") (pinfunction "OUTC_20") (pintype "passive"))
      (node (ref "R380") (pin "1") (pinfunction "1_1") (pintype "passive"))
    )
    (net (code "17") (name "/CTRLR_OUTD") (class "Default")
      (node (ref "IC303") (pin "19") (pinfunction "OUTD_19") (pintype "passive"))
      (node (ref "R384") (pin "1") (pinfunction "1_1") (pintype "passive"))
    )
    (net (code "18") (name "/CTRLR_OUTE") (class "Default")
      (node (ref "IC303") (pin "18") (pinfunction "OUTE_18") (pintype "passive"))
      (node (ref "R391") (pin "1") (pinfunction "1_1") (pintype "passive"))
    )
    (net (code "19") (name "/CTRLR_OUTF") (class "Default")
      (node (ref "IC303") (pin "17") (pinfunction "OUTF_17") (pintype "passive"))
      (node (ref "R395") (pin "1") (pinfunction "1_1") (pintype "passive"))
    )
    (net (code "20") (name "/EA_In") (class "Default")
      (node (ref "D302") (pin "1") (pinfunction "1_1") (pintype "passive"))
      (node (ref "D306") (pin "1") (pinfunction "1_1") (pintype "passive"))
      (node (ref "IC303") (pin "2") (pinfunction "EA+_2") (pintype "passive"))
      (node (ref "R305") (pin "2") (pinfunction "2_2") (pintype "passive"))
      (node (ref "R336") (pin "2") (pinfunction "2_2") (pintype "passive"))
      (node (ref "R352") (pin "2") (pinfunction "2_2") (pintype "passive"))
    )
    (net (code "21") (name "/G_DRV1_VCC") (class "Default")
      (node (ref "C332") (pin "2") (pinfunction "2_2") (pintype "passive"))
      (node (ref "C333") (pin "2") (pinfunction "2_2") (pintype "passive"))
      (node (ref "IC306") (pin "15") (pinfunction "VCC_15") (pintype "passive"))
      (node (ref "L302") (pin "2") (pintype "passive"))
      (node (ref "R303") (pin "1") (pinfunction "1_1") (pintype "passive"))
      (node (ref "R308") (pin "1") (pinfunction "1_1") (pintype "passive"))
      (node (ref "R390") (pin "1") (pinfunction "1_1") (pintype "passive"))
    )
    (net (code "22") (name "/G_DRV2_VCC") (class "Default")
      (node (ref "C343") (pin "2") (pinfunction "2_2") (pintype "passive"))
      (node (ref "C344") (pin "2") (pinfunction "2_2") (pintype "passive"))
      (node (ref "IC307") (pin "15") (pinfunction "VCC_15") (pintype "passive"))
      (node (ref "L304") (pin "2") (pintype "passive"))
      (node (ref "R407") (pin "1") (pinfunction "1_1") (pintype "passive"))
      (node (ref "R408") (pin "1") (pinfunction "1_1") (pintype "passive"))
      (node (ref "R409") (pin "1") (pinfunction "1_1") (pintype "passive"))
    )
    (net (code "23") (name "/G_DRV3_VCC") (class "Default")
      (node (ref "C360") (pin "2") (pinfunction "2_2") (pintype "passive"))
      (node (ref "C361") (pin "2") (pinfunction "2_2") (pintype "passive"))
      (node (ref "IC310") (pin "15") (pinfunction "VCC_15") (pintype "passive"))
      (node (ref "L308") (pin "2") (pintype "passive"))
      (node (ref "R413") (pin "1") (pinfunction "1_1") (pintype "passive"))
      (node (ref "R414") (pin "1") (pinfunction "1_1") (pintype "passive"))
      (node (ref "R415") (pin "1") (pinfunction "1_1") (pintype "passive"))
    )
    (net (code "24") (name "/G_DRV4_VCC") (class "Default")
      (node (ref "C363") (pin "2") (pinfunction "2_2") (pintype "passive"))
      (node (ref "C364") (pin "2") (pinfunction "2_2") (pintype "passive"))
      (node (ref "IC311") (pin "15") (pinfunction "VCC_15") (pintype "passive"))
      (node (ref "L309") (pin "2") (pintype "passive"))
      (node (ref "R419") (pin "1") (pinfunction "1_1") (pintype "passive"))
      (node (ref "R420") (pin "1") (pinfunction "1_1") (pintype "passive"))
      (node (ref "R421") (pin "1") (pinfunction "1_1") (pintype "passive"))
    )
    (net (code "25") (name "/G_DRV_INA") (class "Default")
      (node (ref "IC306") (pin "10") (pinfunction "IN+_10") (pintype "passive"))
      (node (ref "R353") (pin "1") (pinfunction "1_1") (pintype "passive"))
      (node (ref "R355") (pin "1") (pinfunction "1_1") (pintype "passive"))
    )
    (net (code "26") (name "/G_DRV_INB") (class "Default")
      (node (ref "IC307") (pin "10") (pinfunction "IN+_10") (pintype "passive"))
      (node (ref "R361") (pin "1") (pinfunction "1_1") (pintype "passive"))
      (node (ref "R364") (pin "1") (pinfunction "1_1") (pintype "passive"))
    )
    (net (code "27") (name "/G_DRV_INC") (class "Default")
      (node (ref "IC310") (pin "10") (pinfunction "IN+_10") (pintype "passive"))
      (node (ref "R373") (pin "1") (pinfunction "1_1") (pintype "passive"))
      (node (ref "R377") (pin "1") (pinfunction "1_1") (pintype "passive"))
    )
    (net (code "28") (name "/G_DRV_IND") (class "Default")
      (node (ref "IC311") (pin "10") (pinfunction "IN+_10") (pintype "passive"))
      (node (ref "R381") (pin "1") (pinfunction "1_1") (pintype "passive"))
      (node (ref "R382") (pin "1") (pinfunction "1_1") (pintype "passive"))
    )
    (net (code "29") (name "/G_DRV_INE") (class "Default")
      (node (ref "IC304") (pin "2") (pinfunction "INA_2") (pintype "passive"))
      (node (ref "IC304") (pin "4") (pinfunction "INB_4") (pintype "passive"))
      (node (ref "R386") (pin "1") (pinfunction "1_1") (pintype "passive"))
      (node (ref "R388") (pin "1") (pinfunction "1_1") (pintype "passive"))
    )
    (net (code "30") (name "/G_DRV_INF") (class "Default")
      (node (ref "IC305") (pin "2") (pinfunction "INA_2") (pintype "passive"))
      (node (ref "IC305") (pin "4") (pinfunction "INB_4") (pintype "passive"))
      (node (ref "R392") (pin "1") (pinfunction "1_1") (pintype "passive"))
      (node (ref "R393") (pin "1") (pinfunction "1_1") (pintype "passive"))
    )
    (net (code "31") (name "/G_DRV_RDY") (class "Default")
      (node (ref "C370") (pin "2") (pinfunction "2_2") (pintype "passive"))
      (node (ref "C373") (pin "2") (pinfunction "2_2") (pintype "passive"))
      (node (ref "C376") (pin "2") (pinfunction "2_2") (pintype "passive"))
      (node (ref "C379") (pin "2") (pinfunction "2_2") (pintype "passive"))
      (node (ref "IC306") (pin "12") (pinfunction "RDY_12") (pintype "passive"))
      (node (ref "IC307") (pin "12") (pinfunction "RDY_12") (pintype "passive"))
      (node (ref "IC310") (pin "12") (pinfunction "RDY_12") (pintype "passive"))
      (node (ref "IC311") (pin "12") (pinfunction "RDY_12") (pintype "passive"))
      (node (ref "R303") (pin "2") (pinfunction "2_2") (pintype "passive"))
      (node (ref "R407") (pin "2") (pinfunction "2_2") (pintype "passive"))
      (node (ref "R413") (pin "2") (pinfunction "2_2") (pintype "passive"))
      (node (ref "R419") (pin "2") (pinfunction "2_2") (pintype "passive"))
    )
    (net (code "32") (name "/Node_A") (class "Default")
      (node (ref "C300") (pin "1") (pinfunction "1_1") (pintype "passive"))
      (node (ref "C307") (pin "2") (pinfunction "2_2") (pintype "passive"))
      (node (ref "C330") (pin "1") (pinfunction "1_1") (pintype "passive"))
      (node (ref "C331") (pin "1") (pinfunction "1_1") (pintype "passive"))
      (node (ref "C339") (pin "1") (pinfunction "1_1") (pintype "passive"))
      (node (ref "C340") (pin "1") (pinfunction "1_1") (pintype "passive"))
      (node (ref "C342") (pin "1") (pinfunction "1_1") (pintype "passive"))
      (node (ref "C354") (pin "1") (pinfunction "1_1") (pintype "passive"))
      (node (ref "D301") (pin "K") (pintype "passive"))
      (node (ref "IC306") (pin "3") (pinfunction "COM_3") (pintype "passive"))
      (node (ref "IC308") (pin "3") (pinfunction "SHDN_3") (pintype "passive"))
      (node (ref "IC308") (pin "5") (pinfunction "GND_5") (pintype "passive"))
      (node (ref "L303") (pin "1") (pintype "passive"))
      (node (ref "L305") (pin "2") (pintype "passive"))
      (node (ref "R309") (pin "1") (pinfunction "1_1") (pintype "passive"))
      (node (ref "R310") (pin "1") (pinfunction "1_1") (pintype "passive"))
      (node (ref "R326") (pin "1") (pinfunction "1_1") (pintype "passive"))
      (node (ref "R398") (pin "2") (pinfunction "2_2") (pintype "passive"))
      (node (ref "R405") (pin "2") (pinfunction "2_2") (pintype "passive"))
      (node (ref "T301") (pin "3") (pinfunction "E_3") (pintype "passive"))
      (node (ref "T304") (pin "2") (pinfunction "C_2") (pintype "passive"))
      (node (ref "U304") (pin "1") (pintype "passive"))
    )
    (net (code "33") (name "/Node_B") (class "Default")
      (node (ref "C335") (pin "1") (pinfunction "1_1") (pintype "passive"))
      (node (ref "C336") (pin "1") (pinfunction "1_1") (pintype "passive"))
      (node (ref "C345") (pin "1") (pinfunction "1_1") (pintype "passive"))
      (node (ref "C349") (pin "1") (pinfunction "1_1") (pintype "passive"))
      (node (ref "C350") (pin "1") (pinfunction "1_1") (pintype "passive"))
      (node (ref "C352") (pin "2") (pinfunction "2_2") (pintype "passive"))
      (node (ref "C353") (pin "1") (pinfunction "1_1") (pintype "passive"))
      (node (ref "C365") (pin "1") (pinfunction "1_1") (pintype "passive"))
      (node (ref "C366") (pin "1") (pinfunction "1_1") (pintype "passive"))
      (node (ref "C367") (pin "1") (pinfunction "1_1") (pintype "passive"))
      (node (ref "C368") (pin "1") (pinfunction "1_1") (pintype "passive"))
      (node (ref "C369") (pin "1") (pinfunction "1_1") (pintype "passive"))
      (node (ref "IC307") (pin "3") (pinfunction "COM_3") (pintype "passive"))
      (node (ref "IC311") (pin "3") (pinfunction "COM_3") (pintype "passive"))
      (node (ref "R328") (pin "1") (pinfunction "1_1") (pintype "passive"))
      (node (ref "R329") (pin "1") (pinfunction "1_1") (pintype "passive"))
      (node (ref "R330") (pin "1") (pinfunction "1_1") (pintype "passive"))
      (node (ref "R331") (pin "1") (pinfunction "1_1") (pintype "passive"))
      (node (ref "R398") (pin "1") (pinfunction "1_1") (pintype "passive"))
      (node (ref "R411") (pin "2") (pinfunction "2_2") (pintype "passive"))
      (node (ref "R423") (pin "2") (pinfunction "2_2") (pintype "passive"))
      (node (ref "T303") (pin "3") (pinfunction "E_3") (pintype "passive"))
      (node (ref "T304") (pin "3") (pinfunction "E_3") (pintype "passive"))
    )
    (net (code "34") (name "/Node_C") (class "Default")
      (node (ref "C308") (pin "2") (pinfunction "2_2") (pintype "passive"))
      (node (ref "C351") (pin "2") (pinfunction "2_2") (pintype "passive"))
      (node (ref "C355") (pin "1") (pinfunction "1_1") (pintype "passive"))
      (node (ref "C356") (pin "1") (pinfunction "1_1") (pintype "passive"))
      (node (ref "C357") (pin "1") (pinfunction "1_1") (pintype "passive"))
      (node (ref "C358") (pin "1") (pinfunction "1_1") (pintype "passive"))
      (node (ref "C359") (pin "1") (pinfunction "1_1") (pintype "passive"))
      (node (ref "C362") (pin "1") (pinfunction "1_1") (pintype "passive"))
      (node (ref "C386") (pin "1") (pinfunction "1_1") (pintype "passive"))
      (node (ref "D305") (pin "K") (pintype "passive"))
      (node (ref "IC309") (pin "3") (pinfunction "SHDN_3") (pintype "passive"))
      (node (ref "IC309") (pin "5") (pinfunction "GND_5") (pintype "passive"))
      (node (ref "IC310") (pin "3") (pinfunction "COM_3") (pintype "passive"))
      (node (ref "L307") (pin "1") (pintype "passive"))
      (node (ref "R311") (pin "1") (pinfunction "1_1") (pintype "passive"))
      (node (ref "R312") (pin "1") (pinfunction "1_1") (pintype "passive"))
      (node (ref "R417") (pin "2") (pinfunction "2_2") (pintype "passive"))
      (node (ref "T300") (pin "3") (pinfunction "E_3") (pintype "passive"))
      (node (ref "T303") (pin "2") (pinfunction "C_2") (pintype "passive"))
      (node (ref "T305") (pin "6") (pinfunction "6_6") (pintype "passive"))
      (node (ref "U305") (pin "1") (pintype "passive"))
    )
    (net (code "35") (name "/PSFB_EN") (class "Default")
      (node (ref "C324") (pin "1") (pinfunction "1_1") (pintype "passive"))
      (node (ref "IC303") (pin "5") (pinfunction "SS/EN_5") (pintype "passive"))
    )
    (net (code "36") (name "/PWM_I_Set") (class "Default")
      (node (ref "R349") (pin "2") (pinfunction "2_2") (pintype "passive"))
    )
    (net (code "37") (name "/PWM_V_Set") (class "Default")
      (node (ref "R320") (pin "2") (pinfunction "2_2") (pintype "passive"))
    )
    (net (code "38") (name "/QA_Gate") (class "Default")
      (node (ref "C300") (pin "2") (pinfunction "2_2") (pintype "passive"))
      (node (ref "IC306") (pin "7") (pinfunction "CLAMPI_7") (pintype "passive"))
      (node (ref "R309") (pin "2") (pinfunction "2_2") (pintype "passive"))
      (node (ref "R325") (pin "2") (pinfunction "2_2") (pintype "passive"))
      (node (ref "R327") (pin "2") (pinfunction "2_2") (pintype "passive"))
      (node (ref "T301") (pin "1") (pinfunction "GATE_1") (pintype "passive"))
    )
    (net (code "39") (name "/QA_OC") (class "Default")
      (node (ref "C342") (pin "2") (pinfunction "2_2") (pintype "passive"))
      (node (ref "IC306") (pin "2") (pinfunction "OC_2") (pintype "passive"))
      (node (ref "R397") (pin "1") (pinfunction "1_1") (pintype "passive"))
      (node (ref "R404") (pin "1") (pinfunction "1_1") (pintype "passive"))
      (node (ref "R405") (pin "1") (pinfunction "1_1") (pintype "passive"))
    )
    (net (code "40") (name "/QB_Gate") (class "Default")
      (node (ref "C353") (pin "2") (pinfunction "2_2") (pintype "passive"))
      (node (ref "IC307") (pin "7") (pinfunction "CLAMPI_7") (pintype "passive"))
      (node (ref "R304") (pin "2") (pinfunction "2_2") (pintype "passive"))
      (node (ref "R313") (pin "2") (pinfunction "2_2") (pintype "passive"))
      (node (ref "R328") (pin "2") (pinfunction "2_2") (pintype "passive"))
      (node (ref "T304") (pin "1") (pinfunction "GATE_1") (pintype "passive"))
    )
    (net (code "41") (name "/QB_OC") (class "Default")
      (node (ref "C345") (pin "2") (pinfunction "2_2") (pintype "passive"))
      (node (ref "IC307") (pin "2") (pinfunction "OC_2") (pintype "passive"))
      (node (ref "R406") (pin "1") (pinfunction "1_1") (pintype "passive"))
      (node (ref "R410") (pin "1") (pinfunction "1_1") (pintype "passive"))
      (node (ref "R411") (pin "1") (pinfunction "1_1") (pintype "passive"))
    )
    (net (code "42") (name "/QC_Gate") (class "Default")
      (node (ref "C351") (pin "1") (pinfunction "1_1") (pintype "passive"))
      (node (ref "IC310") (pin "7") (pinfunction "CLAMPI_7") (pintype "passive"))
      (node (ref "R312") (pin "2") (pinfunction "2_2") (pintype "passive"))
      (node (ref "R332") (pin "2") (pinfunction "2_2") (pintype "passive"))
      (node (ref "R385") (pin "2") (pinfunction "2_2") (pintype "passive"))
      (node (ref "T300") (pin "1") (pinfunction "GATE_1") (pintype "passive"))
    )
    (net (code "43") (name "/QC_OC") (class "Default")
      (node (ref "C362") (pin "2") (pinfunction "2_2") (pintype "passive"))
      (node (ref "IC310") (pin "2") (pinfunction "OC_2") (pintype "passive"))
      (node (ref "R412") (pin "1") (pinfunction "1_1") (pintype "passive"))
      (node (ref "R416") (pin "1") (pinfunction "1_1") (pintype "passive"))
      (node (ref "R417") (pin "1") (pinfunction "1_1") (pintype "passive"))
    )
    (net (code "44") (name "/QD_Gate") (class "Default")
      (node (ref "C352") (pin "1") (pinfunction "1_1") (pintype "passive"))
      (node (ref "IC311") (pin "7") (pinfunction "CLAMPI_7") (pintype "passive"))
      (node (ref "R331") (pin "2") (pinfunction "2_2") (pintype "passive"))
      (node (ref "R387") (pin "2") (pinfunction "2_2") (pintype "passive"))
      (node (ref "R396") (pin "2") (pinfunction "2_2") (pintype "passive"))
      (node (ref "T303") (pin "1") (pinfunction "GATE_1") (pintype "passive"))
    )
    (net (code "45") (name "/QD_OC") (class "Default")
      (node (ref "C365") (pin "2") (pinfunction "2_2") (pintype "passive"))
      (node (ref "IC311") (pin "2") (pinfunction "OC_2") (pintype "passive"))
      (node (ref "R418") (pin "1") (pinfunction "1_1") (pintype "passive"))
      (node (ref "R422") (pin "1") (pinfunction "1_1") (pintype "passive"))
      (node (ref "R423") (pin "1") (pinfunction "1_1") (pintype "passive"))
    )
    (net (code "46") (name "/VDC360V") (class "Default")
      (node (ref "C303") (pin "2") (pinfunction "2_2") (pintype "passive"))
      (node (ref "C304") (pin "2") (pinfunction "2_2") (pintype "passive"))
      (node (ref "D300") (pin "K") (pintype "passive"))
      (node (ref "D304") (pin "K") (pintype "passive"))
      (node (ref "R326") (pin "2") (pinfunction "2_2") (pintype "passive"))
      (node (ref "T300") (pin "2") (pinfunction "C_2") (pintype "passive"))
      (node (ref "T301") (pin "2") (pinfunction "C_2") (pintype "passive"))
      (node (ref "U301") (pin "1") (pintype "passive"))
      (node (ref "U302") (pin "1") (pintype "passive"))
      (node (ref "U303") (pin "1") (pintype "passive"))
    )
    (net (code "47") (name "/VDD_A") (class "Default")
      (node (ref "C330") (pin "2") (pinfunction "2_2") (pintype "passive"))
      (node (ref "C331") (pin "2") (pinfunction "2_2") (pintype "passive"))
      (node (ref "C382") (pin "1") (pinfunction "1_1") (pintype "passive"))
      (node (ref "C383") (pin "2") (pinfunction "2_2") (pintype "passive"))
      (node (ref "D313") (pin "K") (pintype "passive"))
      (node (ref "IC306") (pin "5") (pinfunction "VDD_5") (pintype "passive"))
      (node (ref "IC308") (pin "6") (pinfunction "V+_6") (pintype "power_in"))
      (node (ref "IC308") (pin "7") (pinfunction "V+_7") (pintype "power_in"))
      (node (ref "R397") (pin "2") (pinfunction "2_2") (pintype "passive"))
    )
    (net (code "48") (name "/VDD_C") (class "Default")
      (node (ref "C357") (pin "2") (pinfunction "2_2") (pintype "passive"))
      (node (ref "C358") (pin "2") (pinfunction "2_2") (pintype "passive"))
      (node (ref "C384") (pin "2") (pinfunction "2_2") (pintype "passive"))
      (node (ref "C385") (pin "1") (pinfunction "1_1") (pintype "passive"))
      (node (ref "C386") (pin "2") (pinfunction "2_2") (pintype "passive"))
      (node (ref "D314") (pin "K") (pintype "passive"))
      (node (ref "IC309") (pin "6") (pinfunction "V+_6") (pintype "power_in"))
      (node (ref "IC309") (pin "7") (pinfunction "V+_7") (pintype "power_in"))
      (node (ref "IC310") (pin "5") (pinfunction "VDD_5") (pintype "passive"))
      (node (ref "R412") (pin "2") (pinfunction "2_2") (pintype "passive"))
    )
    (net (code "49") (name "/VEE_A") (class "Default")
      (node (ref "C339") (pin "2") (pinfunction "2_2") (pintype "passive"))
      (node (ref "C340") (pin "2") (pinfunction "2_2") (pintype "passive"))
      (node (ref "C382") (pin "2") (pinfunction "2_2") (pintype "passive"))
      (node (ref "C383") (pin "1") (pinfunction "1_1") (pintype "passive"))
      (node (ref "D316") (pin "1") (pinfunction "1_1") (pintype "passive"))
      (node (ref "IC306") (pin "8") (pinfunction "VEE_8") (pintype "passive"))
      (node (ref "IC308") (pin "1") (pinfunction "Out_1") (pintype "passive"))
      (node (ref "R399") (pin "1") (pinfunction "1_1") (pintype "passive"))
    )
    (net (code "50") (name "/VEE_B") (class "Default")
      (node (ref "C349") (pin "2") (pinfunction "2_2") (pintype "passive"))
      (node (ref "C350") (pin "2") (pinfunction "2_2") (pintype "passive"))
      (node (ref "C368") (pin "2") (pinfunction "2_2") (pintype "passive"))
      (node (ref "C369") (pin "2") (pinfunction "2_2") (pintype "passive"))
      (node (ref "IC307") (pin "8") (pinfunction "VEE_8") (pintype "passive"))
      (node (ref "IC311") (pin "8") (pinfunction "VEE_8") (pintype "passive"))
    )
    (net (code "51") (name "/VEE_C") (class "Default")
      (node (ref "C355") (pin "2") (pinfunction "2_2") (pintype "passive"))
      (node (ref "C356") (pin "2") (pinfunction "2_2") (pintype "passive"))
      (node (ref "C384") (pin "1") (pinfunction "1_1") (pintype "passive"))
      (node (ref "C385") (pin "2") (pinfunction "2_2") (pintype "passive"))
      (node (ref "D318") (pin "1") (pinfunction "1_1") (pintype "passive"))
      (node (ref "IC309") (pin "1") (pinfunction "Out_1") (pintype "passive"))
      (node (ref "IC310") (pin "8") (pinfunction "VEE_8") (pintype "passive"))
      (node (ref "R402") (pin "1") (pinfunction "1_1") (pintype "passive"))
    )
    (net (code "52") (name "/V_3V3") (class "Default")
      (node (ref "C323") (pin "2") (pinfunction "2_2") (pintype "passive"))
      (node (ref "C325") (pin "2") (pinfunction "2_2") (pintype "passive"))
      (node (ref "C328") (pin "2") (pinfunction "2_2") (pintype "passive"))
      (node (ref "C329") (pin "2") (pinfunction "2_2") (pintype "passive"))
      (node (ref "C334") (pin "2") (pinfunction "2_2") (pintype "passive"))
      (node (ref "C347") (pin "2") (pinfunction "2_2") (pintype "passive"))
      (node (ref "IC301") (pin "5") (pintype "passive"))
      (node (ref "L302") (pin "1") (pintype "passive"))
      (node (ref "L304") (pin "1") (pintype "passive"))
      (node (ref "L308") (pin "1") (pintype "passive"))
      (node (ref "L309") (pin "1") (pintype "passive"))
      (node (ref "T307") (pin "3") (pintype "passive"))
      (node (ref "T308") (pin "3") (pintype "passive"))
      (node (ref "T309") (pin "3") (pintype "passive"))
      (node (ref "T310") (pin "3") (pintype "passive"))
    )
    (net (code "53") (name "/V_5V0") (class "Default")
      (node (ref "C346") (pin "2") (pinfunction "2_2") (pintype "passive"))
      (node (ref "C348") (pin "2") (pinfunction "2_2") (pintype "passive"))
      (node (ref "IC300") (pin "5") (pintype "passive"))
      (node (ref "IC302") (pin "5") (pintype "passive"))
      (node (ref "R319") (pin "2") (pinfunction "2_2") (pintype "passive"))
      (node (ref "R343") (pin "1") (pinfunction "1_1") (pintype "passive"))
      (node (ref "R348") (pin "2") (pinfunction "2_2") (pintype "passive"))
    )
    (net (code "54") (name "/V_12V0") (class "Default")
      (node (ref "C321") (pin "2") (pinfunction "2_2") (pintype "passive"))
      (node (ref "C322") (pin "2") (pinfunction "2_2") (pintype "passive"))
      (node (ref "C326") (pin "2") (pinfunction "2_2") (pintype "passive"))
      (node (ref "C327") (pin "2") (pinfunction "2_2") (pintype "passive"))
      (node (ref "C337") (pin "2") (pinfunction "2_2") (pintype "passive"))
      (node (ref "C338") (pin "2") (pinfunction "2_2") (pintype "passive"))
      (node (ref "C341") (pin "2") (pinfunction "2_2") (pintype "passive"))
      (node (ref "IC304") (pin "6") (pinfunction "VDD_6") (pintype "passive"))
      (node (ref "IC305") (pin "6") (pinfunction "VDD_6") (pintype "passive"))
      (node (ref "L300") (pin "2") (pintype "passive"))
      (node (ref "T311") (pin "3") (pintype "passive"))
      (node (ref "T312") (pin "3") (pintype "passive"))
    )
    (net (code "55") (name "/V_CS_F") (class "Default")
      (node (ref "C306") (pin "2") (pinfunction "2_2") (pintype "passive"))
      (node (ref "IC303") (pin "15") (pinfunction "CS_15") (pintype "passive"))
      (node (ref "R315") (pin "1") (pinfunction "1_1") (pintype "passive"))
      (node (ref "R363") (pin "1") (pinfunction "1_1") (pintype "passive"))
      (node (ref "R366") (pin "1") (pinfunction "1_1") (pintype "passive"))
    )
    (net (code "56") (name "/V_Rect_F_Plus") (class "Default")
      (node (ref "U300") (pin "1") (pintype "passive"))
    )
    (net (code "57") (name "/Vref") (class "Default")
      (node (ref "C319") (pin "1") (pinfunction "1_1") (pintype "passive"))
      (node (ref "IC303") (pin "1") (pinfunction "Vref_1") (pintype "passive"))
      (node (ref "R352") (pin "1") (pinfunction "1_1") (pintype "passive"))
      (node (ref "R368") (pin "2") (pinfunction "2_2") (pintype "passive"))
      (node (ref "R369") (pin "1") (pinfunction "1_1") (pintype "passive"))
      (node (ref "R374") (pin "2") (pinfunction "2_2") (pintype "passive"))
    )
    (net (code "58") (name "/Welder+") (class "Default")
      (node (ref "D307") (pin "2") (pintype "passive"))
      (node (ref "D308") (pin "2") (pintype "passive"))
      (node (ref "D309") (pin "2") (pintype "passive"))
      (node (ref "D310") (pin "2") (pintype "passive"))
      (node (ref "D311") (pin "2") (pintype "passive"))
      (node (ref "D312") (pin "2") (pintype "passive"))
      (node (ref "R307") (pin "2") (pinfunction "2_2") (pintype "passive"))
      (node (ref "U306") (pin "1") (pintype "passive"))
      (node (ref "U307") (pin "1") (pintype "passive"))
      (node (ref "U308") (pin "1") (pintype "passive"))
      (node (ref "U309") (pin "1") (pintype "passive"))
      (node (ref "V300") (pin "2") (pintype "passive"))
    )
    (net (code "59") (name "/Welder-") (class "Default")
      (node (ref "R335") (pin "2") (pinfunction "2_2") (pintype "passive"))
      (node (ref "R340") (pin "2") (pinfunction "2_2") (pintype "passive"))
      (node (ref "V300") (pin "1") (pintype "passive"))
    )
    (net (code "60") (name "/{slash}G_DRV_FaultA") (class "Default")
      (node (ref "C371") (pin "2") (pinfunction "2_2") (pintype "passive"))
      (node (ref "IC306") (pin "13") (pinfunction "/FLT_13") (pintype "passive"))
      (node (ref "R308") (pin "2") (pinfunction "2_2") (pintype "passive"))
    )
    (net (code "61") (name "/{slash}G_DRV_FaultB") (class "Default")
      (node (ref "C374") (pin "2") (pinfunction "2_2") (pintype "passive"))
      (node (ref "IC307") (pin "13") (pinfunction "/FLT_13") (pintype "passive"))
      (node (ref "R408") (pin "2") (pinfunction "2_2") (pintype "passive"))
    )
    (net (code "62") (name "/{slash}G_DRV_FaultC") (class "Default")
      (node (ref "C377") (pin "2") (pinfunction "2_2") (pintype "passive"))
      (node (ref "IC310") (pin "13") (pinfunction "/FLT_13") (pintype "passive"))
      (node (ref "R414") (pin "2") (pinfunction "2_2") (pintype "passive"))
    )
    (net (code "63") (name "/{slash}G_DRV_FaultD") (class "Default")
      (node (ref "C380") (pin "2") (pinfunction "2_2") (pintype "passive"))
      (node (ref "IC311") (pin "13") (pinfunction "/FLT_13") (pintype "passive"))
      (node (ref "R420") (pin "2") (pinfunction "2_2") (pintype "passive"))
    )
    (net (code "64") (name "/{slash}G_DRV_RST") (class "Default")
      (node (ref "C372") (pin "2") (pinfunction "2_2") (pintype "passive"))
      (node (ref "C375") (pin "2") (pinfunction "2_2") (pintype "passive"))
      (node (ref "C378") (pin "2") (pinfunction "2_2") (pintype "passive"))
      (node (ref "C381") (pin "2") (pinfunction "2_2") (pintype "passive"))
      (node (ref "IC306") (pin "14") (pinfunction "/RST_-_EN_14") (pintype "passive"))
      (node (ref "IC307") (pin "14") (pinfunction "/RST_-_EN_14") (pintype "passive"))
      (node (ref "IC310") (pin "14") (pinfunction "/RST_-_EN_14") (pintype "passive"))
      (node (ref "IC311") (pin "14") (pinfunction "/RST_-_EN_14") (pintype "passive"))
      (node (ref "R390") (pin "2") (pinfunction "2_2") (pintype "passive"))
      (node (ref "R409") (pin "2") (pinfunction "2_2") (pintype "passive"))
      (node (ref "R415") (pin "2") (pinfunction "2_2") (pintype "passive"))
      (node (ref "R421") (pin "2") (pinfunction "2_2") (pintype "passive"))
    )
    (net (code "65") (name "GND") (class "Default")
      (node (ref "C306") (pin "1") (pinfunction "1_1") (pintype "passive"))
      (node (ref "C309") (pin "1") (pinfunction "1_1") (pintype "passive"))
      (node (ref "C310") (pin "1") (pinfunction "1_1") (pintype "passive"))
      (node (ref "C314") (pin "1") (pinfunction "1_1") (pintype "passive"))
      (node (ref "C317") (pin "1") (pinfunction "1_1") (pintype "passive"))
      (node (ref "C318") (pin "1") (pinfunction "1_1") (pintype "passive"))
      (node (ref "C319") (pin "2") (pinfunction "2_2") (pintype "passive"))
      (node (ref "C320") (pin "1") (pinfunction "1_1") (pintype "passive"))
      (node (ref "C321") (pin "1") (pinfunction "1_1") (pintype "passive"))
      (node (ref "C322") (pin "1") (pinfunction "1_1") (pintype "passive"))
      (node (ref "C323") (pin "1") (pinfunction "1_1") (pintype "passive"))
      (node (ref "C324") (pin "2") (pinfunction "2_2") (pintype "passive"))
      (node (ref "C325") (pin "1") (pinfunction "1_1") (pintype "passive"))
      (node (ref "C326") (pin "1") (pinfunction "1_1") (pintype "passive"))
      (node (ref "C327") (pin "1") (pinfunction "1_1") (pintype "passive"))
      (node (ref "C328") (pin "1") (pinfunction "1_1") (pintype "passive"))
      (node (ref "C329") (pin "1") (pinfunction "1_1") (pintype "passive"))
      (node (ref "C332") (pin "1") (pinfunction "1_1") (pintype "passive"))
      (node (ref "C333") (pin "1") (pinfunction "1_1") (pintype "passive"))
      (node (ref "C334") (pin "1") (pinfunction "1_1") (pintype "passive"))
      (node (ref "C337") (pin "1") (pinfunction "1_1") (pintype "passive"))
      (node (ref "C338") (pin "1") (pinfunction "1_1") (pintype "passive"))
      (node (ref "C341") (pin "1") (pinfunction "1_1") (pintype "passive"))
      (node (ref "C343") (pin "1") (pinfunction "1_1") (pintype "passive"))
      (node (ref "C344") (pin "1") (pinfunction "1_1") (pintype "passive"))
      (node (ref "C346") (pin "1") (pinfunction "1_1") (pintype "passive"))
      (node (ref "C347") (pin "1") (pinfunction "1_1") (pintype "passive"))
      (node (ref "C348") (pin "1") (pinfunction "1_1") (pintype "passive"))
      (node (ref "C360") (pin "1") (pinfunction "1_1") (pintype "passive"))
      (node (ref "C361") (pin "1") (pinfunction "1_1") (pintype "passive"))
      (node (ref "C363") (pin "1") (pinfunction "1_1") (pintype "passive"))
      (node (ref "C364") (pin "1") (pinfunction "1_1") (pintype "passive"))
      (node (ref "C370") (pin "1") (pinfunction "1_1") (pintype "passive"))
      (node (ref "C371") (pin "1") (pinfunction "1_1") (pintype "passive"))
      (node (ref "C372") (pin "1") (pinfunction "1_1") (pintype "passive"))
      (node (ref "C373") (pin "1") (pinfunction "1_1") (pintype "passive"))
      (node (ref "C374") (pin "1") (pinfunction "1_1") (pintype "passive"))
      (node (ref "C375") (pin "1") (pinfunction "1_1") (pintype "passive"))
      (node (ref "C376") (pin "1") (pinfunction "1_1") (pintype "passive"))
      (node (ref "C377") (pin "1") (pinfunction "1_1") (pintype "passive"))
      (node (ref "C378") (pin "1") (pinfunction "1_1") (pintype "passive"))
      (node (ref "C379") (pin "1") (pinfunction "1_1") (pintype "passive"))
      (node (ref "C380") (pin "1") (pinfunction "1_1") (pintype "passive"))
      (node (ref "C381") (pin "1") (pinfunction "1_1") (pintype "passive"))
      (node (ref "IC300") (pin "2") (pintype "passive"))
      (node (ref "IC301") (pin "2") (pintype "passive"))
      (node (ref "IC302") (pin "2") (pintype "passive"))
      (node (ref "IC303") (pin "24") (pinfunction "GND_24") (pintype "passive"))
      (node (ref "IC304") (pin "3") (pinfunction "GND_3") (pintype "passive"))
      (node (ref "IC305") (pin "3") (pinfunction "GND_3") (pintype "passive"))
      (node (ref "IC306") (pin "11") (pinfunction "IN-_11") (pintype "passive"))
      (node (ref "IC306") (pin "9") (pinfunction "GND_9") (pintype "passive"))
      (node (ref "IC307") (pin "11") (pinfunction "IN-_11") (pintype "passive"))
      (node (ref "IC307") (pin "9") (pinfunction "GND_9") (pintype "passive"))
      (node (ref "IC310") (pin "11") (pinfunction "IN-_11") (pintype "passive"))
      (node (ref "IC310") (pin "9") (pinfunction "GND_9") (pintype "passive"))
      (node (ref "IC311") (pin "11") (pinfunction "IN-_11") (pintype "passive"))
      (node (ref "IC311") (pin "9") (pinfunction "GND_9") (pintype "passive"))
      (node (ref "R316") (pin "1") (pinfunction "1_1") (pintype "passive"))
      (node (ref "R321") (pin "2") (pinfunction "2_2") (pintype "passive"))
      (node (ref "R324") (pin "1") (pinfunction "1_1") (pintype "passive"))
      (node (ref "R334") (pin "1") (pinfunction "1_1") (pintype "passive"))
      (node (ref "R340") (pin "1") (pinfunction "1_1") (pintype "passive"))
      (node (ref "R344") (pin "2") (pinfunction "2_2") (pintype "passive"))
      (node (ref "R350") (pin "2") (pinfunction "2_2") (pintype "passive"))
      (node (ref "R351") (pin "1") (pinfunction "1_1") (pintype "passive"))
      (node (ref "R355") (pin "2") (pinfunction "2_2") (pintype "passive"))
      (node (ref "R357") (pin "1") (pinfunction "1_1") (pintype "passive"))
      (node (ref "R359") (pin "1") (pinfunction "1_1") (pintype "passive"))
      (node (ref "R360") (pin "1") (pinfunction "1_1") (pintype "passive"))
      (node (ref "R362") (pin "1") (pinfunction "1_1") (pintype "passive"))
      (node (ref "R364") (pin "2") (pinfunction "2_2") (pintype "passive"))
      (node (ref "R365") (pin "2") (pinfunction "2_2") (pintype "passive"))
      (node (ref "R371") (pin "1") (pinfunction "1_1") (pintype "passive"))
      (node (ref "R375") (pin "1") (pinfunction "1_1") (pintype "passive"))
      (node (ref "R376") (pin "1") (pinfunction "1_1") (pintype "passive"))
      (node (ref "R377") (pin "2") (pinfunction "2_2") (pintype "passive"))
      (node (ref "R379") (pin "2") (pinfunction "2_2") (pintype "passive"))
      (node (ref "R382") (pin "2") (pinfunction "2_2") (pintype "passive"))
      (node (ref "R388") (pin "2") (pinfunction "2_2") (pintype "passive"))
      (node (ref "R393") (pin "2") (pinfunction "2_2") (pintype "passive"))
      (node (ref "T302") (pin "2") (pintype "passive"))
      (node (ref "T305") (pin "2") (pinfunction "2_2") (pintype "passive"))
      (node (ref "T305") (pin "4") (pinfunction "4_4") (pintype "passive"))
      (node (ref "T306") (pin "2") (pintype "passive"))
      (node (ref "Tr300") (pin "1") (pinfunction "1_1") (pintype "passive"))
    )
    (net (code "66") (name "Net-(C301-Pad1)") (class "Default")
      (node (ref "C301") (pin "1") (pinfunction "1_1") (pintype "passive"))
      (node (ref "C305") (pin "2") (pinfunction "2_2") (pintype "passive"))
      (node (ref "IC300") (pin "4") (pintype "passive"))
      (node (ref "R300") (pin "1") (pinfunction "1_1") (pintype "passive"))
      (node (ref "R306") (pin "2") (pinfunction "2_2") (pintype "passive"))
    )
    (net (code "67") (name "Net-(C301-Pad2)") (class "Default")
      (node (ref "C301") (pin "2") (pinfunction "2_2") (pintype "passive"))
      (node (ref "C302") (pin "2") (pinfunction "2_2") (pintype "passive"))
      (node (ref "D302") (pin "2") (pinfunction "2_2") (pintype "passive"))
      (node (ref "IC300") (pin "1") (pintype "passive"))
      (node (ref "R305") (pin "1") (pinfunction "1_1") (pintype "passive"))
    )
    (net (code "68") (name "Net-(C302-Pad1)") (class "Default")
      (node (ref "C302") (pin "1") (pinfunction "1_1") (pintype "passive"))
      (node (ref "R300") (pin "2") (pinfunction "2_2") (pintype "passive"))
    )
    (net (code "69") (name "Net-(C303-Pad1)") (class "Default")
      (node (ref "C303") (pin "1") (pinfunction "1_1") (pintype "passive"))
      (node (ref "R301") (pin "2") (pinfunction "2_2") (pintype "passive"))
    )
    (net (code "70") (name "Net-(C304-Pad1)") (class "Default")
      (node (ref "C304") (pin "1") (pinfunction "1_1") (pintype "passive"))
      (node (ref "R302") (pin "2") (pinfunction "2_2") (pintype "passive"))
    )
    (net (code "71") (name "Net-(C305-Pad1)") (class "Default")
      (node (ref "C305") (pin "1") (pinfunction "1_1") (pintype "passive"))
      (node (ref "R314") (pin "2") (pinfunction "2_2") (pintype "passive"))
    )
    (net (code "72") (name "Net-(C307-Pad1)") (class "Default")
      (node (ref "C307") (pin "1") (pinfunction "1_1") (pintype "passive"))
      (node (ref "R322") (pin "2") (pinfunction "2_2") (pintype "passive"))
    )
    (net (code "73") (name "Net-(C308-Pad1)") (class "Default")
      (node (ref "C308") (pin "1") (pinfunction "1_1") (pintype "passive"))
      (node (ref "R323") (pin "2") (pinfunction "2_2") (pintype "passive"))
    )
    (net (code "74") (name "Net-(C309-Pad2)") (class "Default")
      (node (ref "C309") (pin "2") (pinfunction "2_2") (pintype "passive"))
      (node (ref "IC300") (pin "3") (pintype "passive"))
      (node (ref "R317") (pin "2") (pinfunction "2_2") (pintype "passive"))
      (node (ref "R321") (pin "1") (pinfunction "1_1") (pintype "passive"))
    )
    (net (code "75") (name "Net-(C310-Pad2)") (class "Default")
      (node (ref "C310") (pin "2") (pinfunction "2_2") (pintype "passive"))
      (node (ref "R317") (pin "1") (pinfunction "1_1") (pintype "passive"))
      (node (ref "R318") (pin "2") (pinfunction "2_2") (pintype "passive"))
    )
    (net (code "76") (name "Net-(C311-Pad1)") (class "Default")
      (node (ref "C311") (pin "1") (pinfunction "1_1") (pintype "passive"))
      (node (ref "C315") (pin "2") (pinfunction "2_2") (pintype "passive"))
      (node (ref "IC302") (pin "4") (pintype "passive"))
      (node (ref "R333") (pin "1") (pinfunction "1_1") (pintype "passive"))
      (node (ref "R338") (pin "2") (pinfunction "2_2") (pintype "passive"))
    )
    (net (code "77") (name "Net-(C311-Pad2)") (class "Default")
      (node (ref "C311") (pin "2") (pinfunction "2_2") (pintype "passive"))
      (node (ref "C312") (pin "2") (pinfunction "2_2") (pintype "passive"))
      (node (ref "D306") (pin "2") (pinfunction "2_2") (pintype "passive"))
      (node (ref "IC302") (pin "1") (pintype "passive"))
      (node (ref "R336") (pin "1") (pinfunction "1_1") (pintype "passive"))
    )
    (net (code "78") (name "Net-(C312-Pad1)") (class "Default")
      (node (ref "C312") (pin "1") (pinfunction "1_1") (pintype "passive"))
      (node (ref "R333") (pin "2") (pinfunction "2_2") (pintype "passive"))
    )
    (net (code "79") (name "Net-(C313-Pad1)") (class "Default")
      (node (ref "C313") (pin "1") (pinfunction "1_1") (pintype "passive"))
      (node (ref "C314") (pin "2") (pinfunction "2_2") (pintype "passive"))
      (node (ref "C316") (pin "2") (pinfunction "2_2") (pintype "passive"))
    )
    (net (code "80") (name "Net-(C313-Pad2)") (class "Default")
      (node (ref "C313") (pin "2") (pinfunction "2_2") (pintype "passive"))
      (node (ref "R335") (pin "1") (pinfunction "1_1") (pintype "passive"))
      (node (ref "R337") (pin "2") (pinfunction "2_2") (pintype "passive"))
    )
    (net (code "81") (name "Net-(C315-Pad1)") (class "Default")
      (node (ref "C315") (pin "1") (pinfunction "1_1") (pintype "passive"))
      (node (ref "R342") (pin "2") (pinfunction "2_2") (pintype "passive"))
    )
    (net (code "82") (name "Net-(C316-Pad1)") (class "Default")
      (node (ref "C316") (pin "1") (pinfunction "1_1") (pintype "passive"))
      (node (ref "R341") (pin "2") (pinfunction "2_2") (pintype "passive"))
      (node (ref "R344") (pin "1") (pinfunction "1_1") (pintype "passive"))
    )
    (net (code "83") (name "Net-(C317-Pad2)") (class "Default")
      (node (ref "C317") (pin "2") (pinfunction "2_2") (pintype "passive"))
      (node (ref "IC302") (pin "3") (pintype "passive"))
      (node (ref "R346") (pin "2") (pinfunction "2_2") (pintype "passive"))
      (node (ref "R350") (pin "1") (pinfunction "1_1") (pintype "passive"))
    )
    (net (code "84") (name "Net-(C318-Pad2)") (class "Default")
      (node (ref "C318") (pin "2") (pinfunction "2_2") (pintype "passive"))
      (node (ref "R346") (pin "1") (pinfunction "1_1") (pintype "passive"))
      (node (ref "R347") (pin "2") (pinfunction "2_2") (pintype "passive"))
    )
    (net (code "85") (name "Net-(D300-PadA)") (class "Default")
      (node (ref "D300") (pin "A") (pintype "passive"))
      (node (ref "R404") (pin "2") (pinfunction "2_2") (pintype "passive"))
    )
    (net (code "86") (name "Net-(D301-PadA)") (class "Default")
      (node (ref "D301") (pin "A") (pintype "passive"))
      (node (ref "R410") (pin "2") (pinfunction "2_2") (pintype "passive"))
    )
    (net (code "87") (name "Net-(D303-PadA)") (class "Default")
      (node (ref "D303") (pin "A") (pintype "passive"))
      (node (ref "Tr300") (pin "2") (pinfunction "2_2") (pintype "passive"))
    )
    (net (code "88") (name "Net-(D303-PadK)") (class "Default")
      (node (ref "D303") (pin "K") (pintype "passive"))
      (node (ref "R315") (pin "2") (pinfunction "2_2") (pintype "passive"))
      (node (ref "R316") (pin "2") (pinfunction "2_2") (pintype "passive"))
    )
    (net (code "89") (name "Net-(D304-PadA)") (class "Default")
      (node (ref "D304") (pin "A") (pintype "passive"))
      (node (ref "R416") (pin "2") (pinfunction "2_2") (pintype "passive"))
    )
    (net (code "90") (name "Net-(D305-PadA)") (class "Default")
      (node (ref "D305") (pin "A") (pintype "passive"))
      (node (ref "R422") (pin "2") (pinfunction "2_2") (pintype "passive"))
    )
    (net (code "91") (name "Net-(D307-Pad1)") (class "Default")
      (node (ref "D307") (pin "1") (pintype "passive"))
      (node (ref "D307") (pin "3") (pintype "passive"))
      (node (ref "D308") (pin "1") (pintype "passive"))
      (node (ref "D308") (pin "3") (pintype "passive"))
      (node (ref "D309") (pin "1") (pintype "passive"))
      (node (ref "D309") (pin "3") (pintype "passive"))
      (node (ref "T305") (pin "5") (pinfunction "5_5") (pintype "passive"))
    )
    (net (code "92") (name "Net-(D310-Pad1)") (class "Default")
      (node (ref "D310") (pin "1") (pintype "passive"))
      (node (ref "D310") (pin "3") (pintype "passive"))
      (node (ref "D311") (pin "1") (pintype "passive"))
      (node (ref "D311") (pin "3") (pintype "passive"))
      (node (ref "D312") (pin "1") (pintype "passive"))
      (node (ref "D312") (pin "3") (pintype "passive"))
      (node (ref "T305") (pin "3") (pinfunction "3_3") (pintype "passive"))
    )
    (net (code "93") (name "Net-(D313-PadA)") (class "Default")
      (node (ref "D313") (pin "A") (pintype "passive"))
      (node (ref "R372") (pin "1") (pinfunction "1_1") (pintype "passive"))
    )
    (net (code "94") (name "Net-(D314-PadA)") (class "Default")
      (node (ref "D314") (pin "A") (pintype "passive"))
      (node (ref "R401") (pin "1") (pinfunction "1_1") (pintype "passive"))
    )
    (net (code "95") (name "Net-(IC301-Pad1)") (class "Default")
      (node (ref "IC301") (pin "1") (pintype "passive"))
      (node (ref "R339") (pin "2") (pinfunction "2_2") (pintype "passive"))
      (node (ref "R345") (pin "2") (pinfunction "2_2") (pintype "passive"))
    )
    (net (code "96") (name "Net-(IC301-Pad3)") (class "Default")
      (node (ref "IC301") (pin "3") (pintype "passive"))
      (node (ref "R334") (pin "2") (pinfunction "2_2") (pintype "passive"))
      (node (ref "R337") (pin "1") (pinfunction "1_1") (pintype "passive"))
    )
    (net (code "97") (name "Net-(IC301-Pad4)") (class "Default")
      (node (ref "IC301") (pin "4") (pintype "passive"))
      (node (ref "R341") (pin "1") (pinfunction "1_1") (pintype "passive"))
      (node (ref "R345") (pin "1") (pinfunction "1_1") (pintype "passive"))
    )
    (net (code "98") (name "Net-(IC303-ADEL)") (class "Default")
      (node (ref "IC303") (pin "14") (pinfunction "ADEL_14") (pintype "passive"))
      (node (ref "R363") (pin "2") (pinfunction "2_2") (pintype "passive"))
      (node (ref "R376") (pin "2") (pinfunction "2_2") (pintype "passive"))
    )
    (net (code "99") (name "Net-(IC303-ADELEF)") (class "Default")
      (node (ref "IC303") (pin "13") (pinfunction "ADELEF_13") (pintype "passive"))
      (node (ref "R366") (pin "2") (pinfunction "2_2") (pintype "passive"))
      (node (ref "R375") (pin "2") (pinfunction "2_2") (pintype "passive"))
    )
    (net (code "100") (name "Net-(IC303-Comp)") (class "Default")
      (node (ref "IC303") (pin "4") (pinfunction "Comp_4") (pintype "passive"))
      (node (ref "R354") (pin "2") (pinfunction "2_2") (pintype "passive"))
    )
    (net (code "101") (name "Net-(IC303-DCM)") (class "Default")
      (node (ref "IC303") (pin "12") (pinfunction "DCM_12") (pintype "passive"))
      (node (ref "R374") (pin "1") (pinfunction "1_1") (pintype "passive"))
      (node (ref "R379") (pin "1") (pinfunction "1_1") (pintype "passive"))
    )
    (net (code "102") (name "Net-(IC303-DELAB)") (class "Default")
      (node (ref "IC303") (pin "6") (pinfunction "DELAB_6") (pintype "passive"))
      (node (ref "R357") (pin "2") (pinfunction "2_2") (pintype "passive"))
    )
    (net (code "103") (name "Net-(IC303-DELCD)") (class "Default")
      (node (ref "IC303") (pin "7") (pinfunction "DELCD_7") (pintype "passive"))
      (node (ref "R359") (pin "2") (pinfunction "2_2") (pintype "passive"))
    )
    (net (code "104") (name "Net-(IC303-DELEF)") (class "Default")
      (node (ref "IC303") (pin "8") (pinfunction "DELEF_8") (pintype "passive"))
      (node (ref "R360") (pin "2") (pinfunction "2_2") (pintype "passive"))
    )
    (net (code "105") (name "Net-(IC303-EA-)") (class "Default")
      (node (ref "IC303") (pin "3") (pinfunction "EA-_3") (pintype "passive"))
      (node (ref "R354") (pin "1") (pinfunction "1_1") (pintype "passive"))
    )
    (net (code "106") (name "Net-(IC303-RT)") (class "Default")
      (node (ref "IC303") (pin "10") (pinfunction "RT_10") (pintype "passive"))
      (node (ref "R365") (pin "1") (pinfunction "1_1") (pintype "passive"))
      (node (ref "R368") (pin "1") (pinfunction "1_1") (pintype "passive"))
    )
    (net (code "107") (name "Net-(IC303-Rsum)") (class "Default")
      (node (ref "IC303") (pin "11") (pinfunction "Rsum_11") (pintype "passive"))
      (node (ref "R369") (pin "2") (pinfunction "2_2") (pintype "passive"))
      (node (ref "R371") (pin "2") (pinfunction "2_2") (pintype "passive"))
    )
    (net (code "108") (name "Net-(IC303-Tmin)") (class "Default")
      (node (ref "IC303") (pin "9") (pinfunction "Tmin_9") (pintype "passive"))
      (node (ref "R362") (pin "2") (pinfunction "2_2") (pintype "passive"))
    )
    (net (code "109") (name "Net-(IC303-VDD)") (class "Default")
      (node (ref "C320") (pin "2") (pinfunction "2_2") (pintype "passive"))
      (node (ref "IC303") (pin "23") (pinfunction "VDD_23") (pintype "passive"))
      (node (ref "L300") (pin "1") (pintype "passive"))
    )
    (net (code "110") (name "Net-(IC308-FB)") (class "Default")
      (node (ref "IC308") (pin "2") (pinfunction "FB_2") (pintype "passive"))
      (node (ref "R399") (pin "2") (pinfunction "2_2") (pintype "passive"))
      (node (ref "R400") (pin "2") (pinfunction "2_2") (pintype "passive"))
    )
    (net (code "111") (name "Net-(IC308-LX)") (class "Default")
      (node (ref "D316") (pin "2") (pinfunction "2_2") (pintype "passive"))
      (node (ref "IC308") (pin "8") (pinfunction "LX_8") (pintype "passive"))
      (node (ref "L303") (pin "2") (pintype "passive"))
    )
    (net (code "112") (name "Net-(IC308-REF)") (class "Default")
      (node (ref "C354") (pin "2") (pinfunction "2_2") (pintype "passive"))
      (node (ref "IC308") (pin "4") (pinfunction "REF_4") (pintype "power_in"))
      (node (ref "R400") (pin "1") (pinfunction "1_1") (pintype "passive"))
    )
    (net (code "113") (name "Net-(IC309-FB)") (class "Default")
      (node (ref "IC309") (pin "2") (pinfunction "FB_2") (pintype "passive"))
      (node (ref "R402") (pin "2") (pinfunction "2_2") (pintype "passive"))
      (node (ref "R403") (pin "2") (pinfunction "2_2") (pintype "passive"))
    )
    (net (code "114") (name "Net-(IC309-LX)") (class "Default")
      (node (ref "D318") (pin "2") (pinfunction "2_2") (pintype "passive"))
      (node (ref "IC309") (pin "8") (pinfunction "LX_8") (pintype "passive"))
      (node (ref "L307") (pin "2") (pintype "passive"))
    )
    (net (code "115") (name "Net-(IC309-REF)") (class "Default")
      (node (ref "C359") (pin "2") (pinfunction "2_2") (pintype "passive"))
      (node (ref "IC309") (pin "4") (pinfunction "REF_4") (pintype "power_in"))
      (node (ref "R403") (pin "1") (pinfunction "1_1") (pintype "passive"))
    )
    (net (code "116") (name "Net-(L301-Pad2)") (class "Default")
      (node (ref "L301") (pin "2") (pintype "passive"))
      (node (ref "R372") (pin "2") (pinfunction "2_2") (pintype "passive"))
    )
    (net (code "117") (name "Net-(L305-Pad1)") (class "Default")
      (node (ref "L305") (pin "1") (pintype "passive"))
      (node (ref "T305") (pin "1") (pinfunction "1_1") (pintype "passive"))
    )
    (net (code "118") (name "Net-(L306-Pad2)") (class "Default")
      (node (ref "L306") (pin "2") (pintype "passive"))
      (node (ref "R401") (pin "2") (pinfunction "2_2") (pintype "passive"))
    )
    (net (code "119") (name "Net-(R301-Pad1)") (class "Default")
      (node (ref "R301") (pin "1") (pinfunction "1_1") (pintype "passive"))
      (node (ref "R310") (pin "2") (pinfunction "2_2") (pintype "passive"))
    )
    (net (code "120") (name "Net-(R302-Pad1)") (class "Default")
      (node (ref "R302") (pin "1") (pinfunction "1_1") (pintype "passive"))
      (node (ref "R311") (pin "2") (pinfunction "2_2") (pintype "passive"))
    )
    (net (code "121") (name "Net-(R306-Pad1)") (class "Default")
      (node (ref "R306") (pin "1") (pinfunction "1_1") (pintype "passive"))
      (node (ref "R307") (pin "1") (pinfunction "1_1") (pintype "passive"))
      (node (ref "R314") (pin "1") (pinfunction "1_1") (pintype "passive"))
    )
    (net (code "122") (name "Net-(R318-Pad1)") (class "Default")
      (node (ref "R318") (pin "1") (pinfunction "1_1") (pintype "passive"))
      (node (ref "R319") (pin "1") (pinfunction "1_1") (pintype "passive"))
      (node (ref "T302") (pin "3") (pintype "passive"))
    )
    (net (code "123") (name "Net-(R320-Pad1)") (class "Default")
      (node (ref "R320") (pin "1") (pinfunction "1_1") (pintype "passive"))
      (node (ref "R324") (pin "2") (pinfunction "2_2") (pintype "passive"))
      (node (ref "T302") (pin "1") (pintype "passive"))
    )
    (net (code "124") (name "Net-(R322-Pad1)") (class "Default")
      (node (ref "R322") (pin "1") (pinfunction "1_1") (pintype "passive"))
      (node (ref "R329") (pin "2") (pinfunction "2_2") (pintype "passive"))
    )
    (net (code "125") (name "Net-(R323-Pad1)") (class "Default")
      (node (ref "R323") (pin "1") (pinfunction "1_1") (pintype "passive"))
      (node (ref "R330") (pin "2") (pinfunction "2_2") (pintype "passive"))
    )
    (net (code "126") (name "Net-(R338-Pad1)") (class "Default")
      (node (ref "R338") (pin "1") (pinfunction "1_1") (pintype "passive"))
      (node (ref "R339") (pin "1") (pinfunction "1_1") (pintype "passive"))
      (node (ref "R342") (pin "1") (pinfunction "1_1") (pintype "passive"))
      (node (ref "R343") (pin "2") (pinfunction "2_2") (pintype "passive"))
    )
    (net (code "127") (name "Net-(R347-Pad1)") (class "Default")
      (node (ref "R347") (pin "1") (pinfunction "1_1") (pintype "passive"))
      (node (ref "R348") (pin "1") (pinfunction "1_1") (pintype "passive"))
      (node (ref "T306") (pin "3") (pintype "passive"))
    )
    (net (code "128") (name "Net-(R349-Pad1)") (class "Default")
      (node (ref "R349") (pin "1") (pinfunction "1_1") (pintype "passive"))
      (node (ref "R351") (pin "2") (pinfunction "2_2") (pintype "passive"))
      (node (ref "T306") (pin "1") (pintype "passive"))
    )
    (net (code "129") (name "Net-(R353-Pad2)") (class "Default")
      (node (ref "R353") (pin "2") (pinfunction "2_2") (pintype "passive"))
      (node (ref "R356") (pin "2") (pinfunction "2_2") (pintype "passive"))
      (node (ref "T307") (pin "2") (pintype "passive"))
    )
    (net (code "130") (name "Net-(R356-Pad1)") (class "Default")
      (node (ref "R356") (pin "1") (pinfunction "1_1") (pintype "passive"))
      (node (ref "R358") (pin "2") (pinfunction "2_2") (pintype "passive"))
      (node (ref "T307") (pin "1") (pintype "passive"))
    )
    (net (code "131") (name "Net-(R361-Pad2)") (class "Default")
      (node (ref "R361") (pin "2") (pinfunction "2_2") (pintype "passive"))
      (node (ref "R367") (pin "2") (pinfunction "2_2") (pintype "passive"))
      (node (ref "T308") (pin "2") (pintype "passive"))
    )
    (net (code "132") (name "Net-(R367-Pad1)") (class "Default")
      (node (ref "R367") (pin "1") (pinfunction "1_1") (pintype "passive"))
      (node (ref "R370") (pin "2") (pinfunction "2_2") (pintype "passive"))
      (node (ref "T308") (pin "1") (pintype "passive"))
    )
    (net (code "133") (name "Net-(R373-Pad2)") (class "Default")
      (node (ref "R373") (pin "2") (pinfunction "2_2") (pintype "passive"))
      (node (ref "R378") (pin "2") (pinfunction "2_2") (pintype "passive"))
      (node (ref "T309") (pin "2") (pintype "passive"))
    )
    (net (code "134") (name "Net-(R378-Pad1)") (class "Default")
      (node (ref "R378") (pin "1") (pinfunction "1_1") (pintype "passive"))
      (node (ref "R380") (pin "2") (pinfunction "2_2") (pintype "passive"))
      (node (ref "T309") (pin "1") (pintype "passive"))
    )
    (net (code "135") (name "Net-(R381-Pad2)") (class "Default")
      (node (ref "R381") (pin "2") (pinfunction "2_2") (pintype "passive"))
      (node (ref "R383") (pin "2") (pinfunction "2_2") (pintype "passive"))
      (node (ref "T310") (pin "2") (pintype "passive"))
    )
    (net (code "136") (name "Net-(R383-Pad1)") (class "Default")
      (node (ref "R383") (pin "1") (pinfunction "1_1") (pintype "passive"))
      (node (ref "R384") (pin "2") (pinfunction "2_2") (pintype "passive"))
      (node (ref "T310") (pin "1") (pintype "passive"))
    )
    (net (code "137") (name "Net-(R386-Pad2)") (class "Default")
      (node (ref "R386") (pin "2") (pinfunction "2_2") (pintype "passive"))
      (node (ref "R389") (pin "2") (pinfunction "2_2") (pintype "passive"))
      (node (ref "T311") (pin "2") (pintype "passive"))
    )
    (net (code "138") (name "Net-(R389-Pad1)") (class "Default")
      (node (ref "R389") (pin "1") (pinfunction "1_1") (pintype "passive"))
      (node (ref "R391") (pin "2") (pinfunction "2_2") (pintype "passive"))
      (node (ref "T311") (pin "1") (pintype "passive"))
    )
    (net (code "139") (name "Net-(R392-Pad2)") (class "Default")
      (node (ref "R392") (pin "2") (pinfunction "2_2") (pintype "passive"))
      (node (ref "R394") (pin "2") (pinfunction "2_2") (pintype "passive"))
      (node (ref "T312") (pin "2") (pintype "passive"))
    )
    (net (code "140") (name "Net-(R394-Pad1)") (class "Default")
      (node (ref "R394") (pin "1") (pinfunction "1_1") (pintype "passive"))
      (node (ref "R395") (pin "2") (pinfunction "2_2") (pintype "passive"))
      (node (ref "T312") (pin "1") (pintype "passive"))
    )
    (net (code "141") (name "V_12V0_Aux") (class "Default")
      (node (ref "C335") (pin "2") (pinfunction "2_2") (pintype "passive"))
      (node (ref "C336") (pin "2") (pinfunction "2_2") (pintype "passive"))
      (node (ref "C366") (pin "2") (pinfunction "2_2") (pintype "passive"))
      (node (ref "C367") (pin "2") (pinfunction "2_2") (pintype "passive"))
      (node (ref "IC307") (pin "5") (pinfunction "VDD_5") (pintype "passive"))
      (node (ref "IC311") (pin "5") (pinfunction "VDD_5") (pintype "passive"))
      (node (ref "L301") (pin "1") (pintype "passive"))
      (node (ref "L306") (pin "1") (pintype "passive"))
      (node (ref "R406") (pin "2") (pinfunction "2_2") (pintype "passive"))
      (node (ref "R418") (pin "2") (pinfunction "2_2") (pintype "passive"))
    )
    (net (code "142") (name "unconnected-(IC303-Sync-Pad16)") (class "Default")
      (node (ref "IC303") (pin "16") (pinfunction "Sync_16") (pintype "passive"))
    )
    (net (code "143") (name "unconnected-(IC304-ENA-Pad1)") (class "Default")
      (node (ref "IC304") (pin "1") (pinfunction "ENA_1") (pintype "passive"))
    )
    (net (code "144") (name "unconnected-(IC304-ENB-Pad8)") (class "Default")
      (node (ref "IC304") (pin "8") (pinfunction "ENB_8") (pintype "passive"))
    )
    (net (code "145") (name "unconnected-(IC305-ENA-Pad1)") (class "Default")
      (node (ref "IC305") (pin "1") (pinfunction "ENA_1") (pintype "passive"))
    )
    (net (code "146") (name "unconnected-(IC305-ENB-Pad8)") (class "Default")
      (node (ref "IC305") (pin "8") (pinfunction "ENB_8") (pintype "passive"))
    )
    (net (code "147") (name "unconnected-(IC306-AIN-Pad1)") (class "Default")
      (node (ref "IC306") (pin "1") (pinfunction "AIN_1") (pintype "passive+no_connect"))
    )
    (net (code "148") (name "unconnected-(IC306-APWM-Pad16)") (class "Default")
      (node (ref "IC306") (pin "16") (pinfunction "APWM_16") (pintype "passive+no_connect"))
    )
    (net (code "149") (name "unconnected-(IC307-AIN-Pad1)") (class "Default")
      (node (ref "IC307") (pin "1") (pinfunction "AIN_1") (pintype "passive+no_connect"))
    )
    (net (code "150") (name "unconnected-(IC307-APWM-Pad16)") (class "Default")
      (node (ref "IC307") (pin "16") (pinfunction "APWM_16") (pintype "passive+no_connect"))
    )
    (net (code "151") (name "unconnected-(IC310-AIN-Pad1)") (class "Default")
      (node (ref "IC310") (pin "1") (pinfunction "AIN_1") (pintype "passive+no_connect"))
    )
    (net (code "152") (name "unconnected-(IC310-APWM-Pad16)") (class "Default")
      (node (ref "IC310") (pin "16") (pinfunction "APWM_16") (pintype "passive+no_connect"))
    )
    (net (code "153") (name "unconnected-(IC311-AIN-Pad1)") (class "Default")
      (node (ref "IC311") (pin "1") (pinfunction "AIN_1") (pintype "passive"))
    )
    (net (code "154") (name "unconnected-(IC311-APWM-Pad16)") (class "Default")
      (node (ref "IC311") (pin "16") (pinfunction "APWM_16") (pintype "passive+no_connect"))
    )
  )
)
